# SCH_SPEAR.net
KiCad netlist of a schematic drawn in EasyEDA
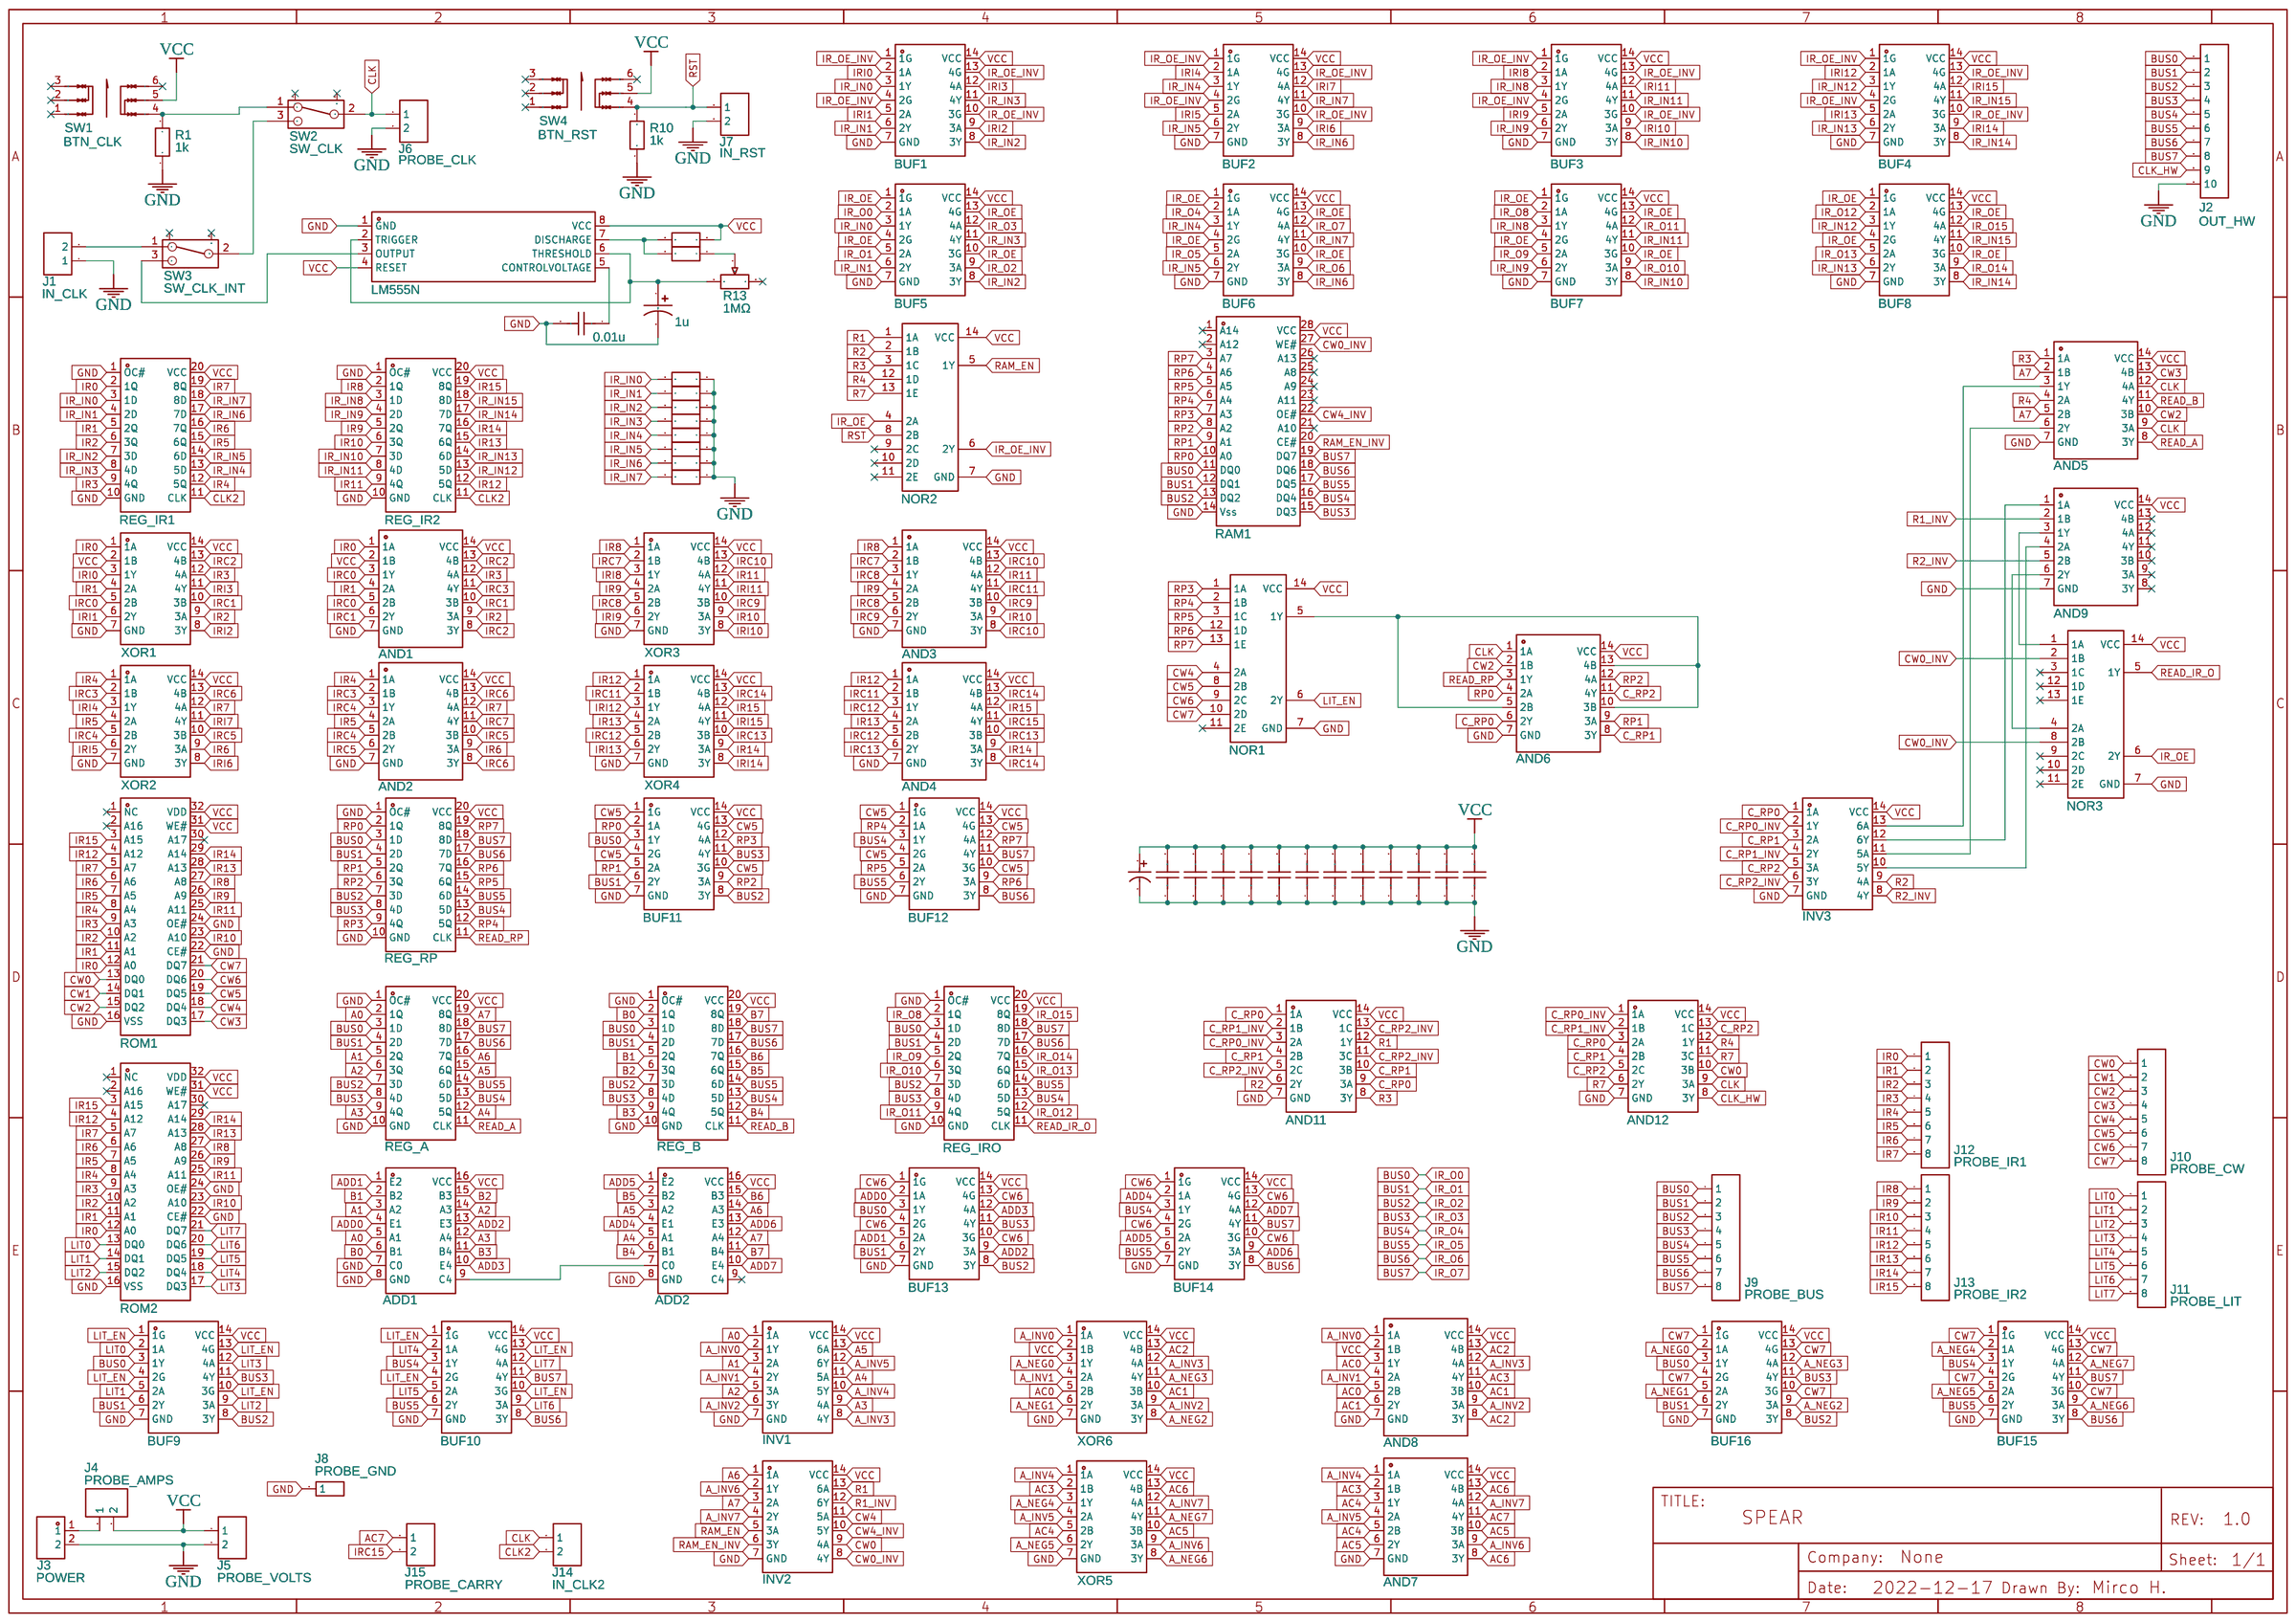
[diagram p0: schematic sheet]

(export (version "E")
  (design (tool "Eeschema 10.0.6"))
  (components
    (comp (ref "ADD1")
      (value "XD74LS283")
      (fields (field (name "BOM_Supplier Part") "C561301"))
      (libsource (lib "") (part "XD74LS283"))
    )
    (comp (ref "ADD2")
      (value "XD74LS283")
      (fields (field (name "BOM_Supplier Part") "C561301"))
      (libsource (lib "") (part "XD74LS283"))
    )
    (comp (ref "AND1")
      (value "SN74LS08DR")
      (fields (field (name "BOM_Supplier Part") "C6802"))
      (libsource (lib "") (part "SN74LS08DR"))
    )
    (comp (ref "AND2")
      (value "SN74LS08DR")
      (fields (field (name "BOM_Supplier Part") "C6802"))
      (libsource (lib "") (part "SN74LS08DR"))
    )
    (comp (ref "AND3")
      (value "SN74LS08DR")
      (fields (field (name "BOM_Supplier Part") "C6802"))
      (libsource (lib "") (part "SN74LS08DR"))
    )
    (comp (ref "AND4")
      (value "SN74LS08DR")
      (fields (field (name "BOM_Supplier Part") "C6802"))
      (libsource (lib "") (part "SN74LS08DR"))
    )
    (comp (ref "AND5")
      (value "SN74LS08DR")
      (fields (field (name "BOM_Supplier Part") "C6802"))
      (libsource (lib "") (part "SN74LS08DR"))
    )
    (comp (ref "AND6")
      (value "SN74LS08DR")
      (fields (field (name "BOM_Supplier Part") "C6802"))
      (libsource (lib "") (part "SN74LS08DR"))
    )
    (comp (ref "AND7")
      (value "SN74LS08DR")
      (fields (field (name "BOM_Supplier Part") "C6802"))
      (libsource (lib "") (part "SN74LS08DR"))
    )
    (comp (ref "AND8")
      (value "SN74LS08DR")
      (fields (field (name "BOM_Supplier Part") "C6802"))
      (libsource (lib "") (part "SN74LS08DR"))
    )
    (comp (ref "AND9")
      (value "SN74LS08DR")
      (fields (field (name "BOM_Supplier Part") "C6802"))
      (libsource (lib "") (part "SN74LS08DR"))
    )
    (comp (ref "AND11")
      (value "XL74LS11")
      (fields (field (name "BOM_Supplier Part") "C521168"))
      (libsource (lib "") (part "XL74LS11"))
    )
    (comp (ref "AND12")
      (value "XL74LS11")
      (fields (field (name "BOM_Supplier Part") "C521168"))
      (libsource (lib "") (part "XL74LS11"))
    )
    (comp (ref "BUF1")
      (value "SN74LS126ADR")
      (fields (field (name "BOM_Supplier Part") "C2865257"))
      (libsource (lib "") (part "SN74LS126ADR"))
    )
    (comp (ref "BUF2")
      (value "SN74LS126ADR")
      (fields (field (name "BOM_Supplier Part") "C2865257"))
      (libsource (lib "") (part "SN74LS126ADR"))
    )
    (comp (ref "BUF3")
      (value "SN74LS126ADR")
      (fields (field (name "BOM_Supplier Part") "C2865257"))
      (libsource (lib "") (part "SN74LS126ADR"))
    )
    (comp (ref "BUF4")
      (value "SN74LS126ADR")
      (fields (field (name "BOM_Supplier Part") "C2865257"))
      (libsource (lib "") (part "SN74LS126ADR"))
    )
    (comp (ref "BUF5")
      (value "SN74LS126ADR")
      (fields (field (name "BOM_Supplier Part") "C2865257"))
      (libsource (lib "") (part "SN74LS126ADR"))
    )
    (comp (ref "BUF6")
      (value "SN74LS126ADR")
      (fields (field (name "BOM_Supplier Part") "C2865257"))
      (libsource (lib "") (part "SN74LS126ADR"))
    )
    (comp (ref "BUF7")
      (value "SN74LS126ADR")
      (fields (field (name "BOM_Supplier Part") "C2865257"))
      (libsource (lib "") (part "SN74LS126ADR"))
    )
    (comp (ref "BUF8")
      (value "SN74LS126ADR")
      (fields (field (name "BOM_Supplier Part") "C2865257"))
      (libsource (lib "") (part "SN74LS126ADR"))
    )
    (comp (ref "BUF9")
      (value "SN74LS126ADR")
      (fields (field (name "BOM_Supplier Part") "C2865257"))
      (libsource (lib "") (part "SN74LS126ADR"))
    )
    (comp (ref "BUF10")
      (value "SN74LS126ADR")
      (fields (field (name "BOM_Supplier Part") "C2865257"))
      (libsource (lib "") (part "SN74LS126ADR"))
    )
    (comp (ref "BUF11")
      (value "SN74LS126ADR")
      (fields (field (name "BOM_Supplier Part") "C2865257"))
      (libsource (lib "") (part "SN74LS126ADR"))
    )
    (comp (ref "BUF12")
      (value "SN74LS126ADR")
      (fields (field (name "BOM_Supplier Part") "C2865257"))
      (libsource (lib "") (part "SN74LS126ADR"))
    )
    (comp (ref "BUF13")
      (value "SN74LS126ADR")
      (fields (field (name "BOM_Supplier Part") "C2865257"))
      (libsource (lib "") (part "SN74LS126ADR"))
    )
    (comp (ref "BUF14")
      (value "SN74LS126ADR")
      (fields (field (name "BOM_Supplier Part") "C2865257"))
      (libsource (lib "") (part "SN74LS126ADR"))
    )
    (comp (ref "BUF15")
      (value "SN74LS126ADR")
      (fields (field (name "BOM_Supplier Part") "C2865257"))
      (libsource (lib "") (part "SN74LS126ADR"))
    )
    (comp (ref "BUF16")
      (value "SN74LS126ADR")
      (fields (field (name "BOM_Supplier Part") "C2865257"))
      (libsource (lib "") (part "SN74LS126ADR"))
    )
    (comp (ref "C1") (value "0.1u") (libsource (lib "") (part "C_0603_US")))
    (comp (ref "C2") (value "0.01u") (libsource (lib "") (part "C_0603_US_1")))
    (comp (ref "C3") (value "1u") (libsource (lib "") (part "C_Tan_SMD_A_US")))
    (comp (ref "C4") (value "0.1u") (libsource (lib "") (part "C_0603_US")))
    (comp (ref "C5") (value "0.1u") (libsource (lib "") (part "C_0603_US")))
    (comp (ref "C6") (value "0.1u") (libsource (lib "") (part "C_0603_US")))
    (comp (ref "C7") (value "0.1u") (libsource (lib "") (part "C_0603_US")))
    (comp (ref "C8") (value "0.1u") (libsource (lib "") (part "C_0603_US")))
    (comp (ref "C9") (value "0.1u") (libsource (lib "") (part "C_0603_US")))
    (comp (ref "C10") (value "0.1u") (libsource (lib "") (part "C_0603_US")))
    (comp (ref "C11") (value "0.1u") (libsource (lib "") (part "C_0603_US")))
    (comp (ref "C12") (value "0.1u") (libsource (lib "") (part "C_0603_US")))
    (comp (ref "C13") (value "0.1u") (libsource (lib "") (part "C_0603_US")))
    (comp (ref "C14") (value "0.1u") (libsource (lib "") (part "C_0603_US")))
    (comp (ref "C15")
      (value "1000uF")
      (fields
        (field (name "BOM_Manufacturer Part") "KM108M025G17RR0VH2FP0")
        (field (name "BOM_Supplier Part") "C10750")
      )
      (libsource (lib "") (part "1000uF 25V"))
    )
    (comp (ref "INV1")
      (value "XL74LS04")
      (fields (field (name "BOM_Supplier Part") "C513511"))
      (libsource (lib "") (part "XL74LS04"))
    )
    (comp (ref "INV2")
      (value "XL74LS04")
      (fields (field (name "BOM_Supplier Part") "C513511"))
      (libsource (lib "") (part "XL74LS04"))
    )
    (comp (ref "INV3")
      (value "XL74LS04")
      (fields (field (name "BOM_Supplier Part") "C513511"))
      (libsource (lib "") (part "XL74LS04"))
    )
    (comp (ref "J1")
      (value "IN_CLK")
      (fields (field (name "BOM_Supplier Part") "C124375"))
      (libsource (lib "") (part "HDR-M-2.54_1x2"))
    )
    (comp (ref "J2")
      (value "OUT_HW")
      (fields (field (name "BOM_Supplier Part") "C57369"))
      (libsource (lib "") (part "HDR-M-2.54_1x10"))
    )
    (comp (ref "J3")
      (value "POWER")
      (fields
        (field (name "BOM_Manufacturer Part") "DB126V-5.0-2P-GN-P")
        (field (name "BOM_Supplier Part") "C395849")
      )
      (libsource (lib "") (part "DB126V-5.0-2P"))
    )
    (comp (ref "J4")
      (value "PROBE_AMPS")
      (fields (field (name "BOM_Supplier Part") "C124375"))
      (libsource (lib "") (part "HDR-M-2.54_1x2_2"))
    )
    (comp (ref "J5")
      (value "PROBE_VOLTS")
      (fields (field (name "BOM_Supplier Part") "C124375"))
      (libsource (lib "") (part "HDR-M-2.54_1x2_1"))
    )
    (comp (ref "J6")
      (value "PROBE_CLK")
      (fields (field (name "BOM_Supplier Part") "C124375"))
      (libsource (lib "") (part "HDR-M-2.54_1x2_1"))
    )
    (comp (ref "J7")
      (value "IN_RST")
      (fields (field (name "BOM_Supplier Part") "C124375"))
      (libsource (lib "") (part "HDR-M-2.54_1x2_1"))
    )
    (comp (ref "J8")
      (value "PROBE_GND")
      (fields (field (name "BOM_Supplier Part") "C81276"))
      (libsource (lib "") (part "HDR-M-2.54_1x1"))
    )
    (comp (ref "J9")
      (value "PROBE_BUS")
      (fields (field (name "BOM_Supplier Part") "C190820"))
      (libsource (lib "") (part "HDR-M-2.54_1x8"))
    )
    (comp (ref "J10")
      (value "PROBE_CW")
      (fields (field (name "BOM_Supplier Part") "C190820"))
      (libsource (lib "") (part "HDR-M-2.54_1x8"))
    )
    (comp (ref "J11")
      (value "PROBE_LIT")
      (fields (field (name "BOM_Supplier Part") "C190820"))
      (libsource (lib "") (part "HDR-M-2.54_1x8"))
    )
    (comp (ref "J12")
      (value "PROBE_IR1")
      (fields (field (name "BOM_Supplier Part") "C190820"))
      (libsource (lib "") (part "HDR-M-2.54_1x8"))
    )
    (comp (ref "J13")
      (value "PROBE_IR2")
      (fields (field (name "BOM_Supplier Part") "C190820"))
      (libsource (lib "") (part "HDR-M-2.54_1x8"))
    )
    (comp (ref "J14")
      (value "IN_CLK2")
      (fields (field (name "BOM_Supplier Part") "C124375"))
      (libsource (lib "") (part "HDR-M-2.54_1x2_1"))
    )
    (comp (ref "J15")
      (value "PROBE_CARRY")
      (fields (field (name "BOM_Supplier Part") "C124375"))
      (libsource (lib "") (part "HDR-M-2.54_1x2_1"))
    )
    (comp (ref "NOR1") (value "LISA_CPU_74LS260") (libsource (lib "") (part "LISA_CPU_74LS260")))
    (comp (ref "NOR2") (value "LISA_CPU_74LS260") (libsource (lib "") (part "LISA_CPU_74LS260")))
    (comp (ref "NOR3") (value "LISA_CPU_74LS260") (libsource (lib "") (part "LISA_CPU_74LS260")))
    (comp (ref "R1") (value "1k") (libsource (lib "") (part "R_0603_EU_1")))
    (comp (ref "R2") (value "10k") (libsource (lib "") (part "R_0603_EU")))
    (comp (ref "R3") (value "10k") (libsource (lib "") (part "R_0603_EU")))
    (comp (ref "R4") (value "10k") (libsource (lib "") (part "R_0603_EU")))
    (comp (ref "R5") (value "10k") (libsource (lib "") (part "R_0603_EU")))
    (comp (ref "R6") (value "10k") (libsource (lib "") (part "R_0603_EU")))
    (comp (ref "R7") (value "10k") (libsource (lib "") (part "R_0603_EU")))
    (comp (ref "R8") (value "10k") (libsource (lib "") (part "R_0603_EU")))
    (comp (ref "R9") (value "10k") (libsource (lib "") (part "R_0603_EU")))
    (comp (ref "R10") (value "1k") (libsource (lib "") (part "R_0603_EU_1")))
    (comp (ref "R11") (value "1k") (libsource (lib "") (part "R_0603_EU")))
    (comp (ref "R12") (value "1k") (libsource (lib "") (part "R_0603_EU")))
    (comp (ref "R13")
      (value "1MΩ")
      (fields
        (field (name "BOM_Manufacturer Part") "3362P-1-105")
        (field (name "BOM_Supplier Part") "C118945")
      )
      (libsource (lib "") (part "3362P-1-105_C118945"))
    )
    (comp (ref "RAM1")
      (value "LY62256SL-70LL")
      (fields (field (name "BOM_Supplier Part") "C261867"))
      (libsource (lib "") (part "LY62256SL-70LL"))
    )
    (comp (ref "REG1")
      (value "REG_IR1")
      (fields
        (field (name "BOM_Manufacturer Part") "SN74LS374NSR")
        (field (name "BOM_Supplier Part") "C7764")
      )
      (libsource (lib "") (part "SN74LS374NSR_2"))
    )
    (comp (ref "REG2")
      (value "REG_IR2")
      (fields
        (field (name "BOM_Manufacturer Part") "SN74LS374NSR")
        (field (name "BOM_Supplier Part") "C7764")
      )
      (libsource (lib "") (part "SN74LS374NSR_2"))
    )
    (comp (ref "REG_A")
      (value "SN74LS374NSR")
      (fields (field (name "BOM_Supplier Part") "C7764"))
      (libsource (lib "") (part "SN74LS374NSR_4"))
    )
    (comp (ref "REG_B")
      (value "SN74LS374NSR")
      (fields (field (name "BOM_Supplier Part") "C7764"))
      (libsource (lib "") (part "SN74LS374NSR"))
    )
    (comp (ref "REG_IRO")
      (value "SN74LS374NSR")
      (fields (field (name "BOM_Supplier Part") "C7764"))
      (libsource (lib "") (part "SN74LS374NSR_1"))
    )
    (comp (ref "REG_RP")
      (value "SN74LS374NSR")
      (fields (field (name "BOM_Supplier Part") "C7764"))
      (libsource (lib "") (part "SN74LS374NSR_3"))
    )
    (comp (ref "ROM1")
      (value "SST39SF020A-70-4I-NHE")
      (fields (field (name "BOM_Supplier Part") "C645934"))
      (libsource (lib "") (part "SST39SF020A-70-4I-NHE"))
    )
    (comp (ref "ROM2")
      (value "SST39SF020A-70-4I-NHE")
      (fields (field (name "BOM_Supplier Part") "C645934"))
      (libsource (lib "") (part "SST39SF020A-70-4I-NHE"))
    )
    (comp (ref "SW1")
      (value "BTN_CLK")
      (fields (field (name "BOM_Manufacturer Part") "XKB8080-W") (field (name "BOM_Supplier Part") "C318861"))
      (libsource (lib "") (part "XKB8080-W"))
    )
    (comp (ref "SW2")
      (value "SW_CLK")
      (fields
        (field (name "BOM_Manufacturer Part") "SK-12E12-G5")
        (field (name "BOM_Supplier Part") "C136720")
      )
      (libsource (lib "") (part "SK-12E12-G5"))
    )
    (comp (ref "SW3")
      (value "SW_CLK_INT")
      (fields
        (field (name "BOM_Manufacturer Part") "SK-12E12-G5")
        (field (name "BOM_Supplier Part") "C136720")
      )
      (libsource (lib "") (part "SK-12E12-G5"))
    )
    (comp (ref "SW4")
      (value "BTN_RST")
      (fields (field (name "BOM_Manufacturer Part") "XKB8080-W") (field (name "BOM_Supplier Part") "C318861"))
      (libsource (lib "") (part "XKB8080-W"))
    )
    (comp (ref "U1")
      (value "LM555N")
      (fields (field (name "BOM_Supplier Part") "C725327"))
      (libsource (lib "") (part "LM555N"))
    )
    (comp (ref "XOR1")
      (value "XD74LS86")
      (fields (field (name "BOM_Supplier Part") "C556290"))
      (libsource (lib "") (part "XD74LS86"))
    )
    (comp (ref "XOR2")
      (value "XD74LS86")
      (fields (field (name "BOM_Supplier Part") "C556290"))
      (libsource (lib "") (part "XD74LS86"))
    )
    (comp (ref "XOR3")
      (value "XD74LS86")
      (fields (field (name "BOM_Supplier Part") "C556290"))
      (libsource (lib "") (part "XD74LS86"))
    )
    (comp (ref "XOR4")
      (value "XD74LS86")
      (fields (field (name "BOM_Supplier Part") "C556290"))
      (libsource (lib "") (part "XD74LS86"))
    )
    (comp (ref "XOR5")
      (value "XD74LS86")
      (fields (field (name "BOM_Supplier Part") "C556290"))
      (libsource (lib "") (part "XD74LS86"))
    )
    (comp (ref "XOR6")
      (value "XD74LS86")
      (fields (field (name "BOM_Supplier Part") "C556290"))
      (libsource (lib "") (part "XD74LS86"))
    )
  )
  (nets
    (net (code "1") (name "A0") (class "Default")
      (node (ref "ADD1") (pin "5") (pinfunction "A1_5") (pintype "unspecified"))
      (node (ref "INV1") (pin "1") (pinfunction "1A_1") (pintype "unspecified"))
      (node (ref "REG_A") (pin "2") (pinfunction "1Q_2") (pintype "unspecified"))
    )
    (net (code "2") (name "A1") (class "Default")
      (node (ref "ADD1") (pin "3") (pinfunction "A2_3") (pintype "unspecified"))
      (node (ref "INV1") (pin "3") (pinfunction "2A_3") (pintype "unspecified"))
      (node (ref "REG_A") (pin "5") (pinfunction "2Q_5") (pintype "unspecified"))
    )
    (net (code "3") (name "A2") (class "Default")
      (node (ref "ADD1") (pin "14") (pinfunction "A3_14") (pintype "unspecified"))
      (node (ref "INV1") (pin "5") (pinfunction "3A_5") (pintype "unspecified"))
      (node (ref "REG_A") (pin "6") (pinfunction "3Q_6") (pintype "unspecified"))
    )
    (net (code "4") (name "A3") (class "Default")
      (node (ref "ADD1") (pin "12") (pinfunction "A4_12") (pintype "unspecified"))
      (node (ref "INV1") (pin "9") (pinfunction "4A_9") (pintype "unspecified"))
      (node (ref "REG_A") (pin "9") (pinfunction "4Q_9") (pintype "unspecified"))
    )
    (net (code "5") (name "A4") (class "Default")
      (node (ref "ADD2") (pin "5") (pinfunction "A1_5") (pintype "unspecified"))
      (node (ref "INV1") (pin "11") (pinfunction "5A_11") (pintype "unspecified"))
      (node (ref "REG_A") (pin "12") (pinfunction "5Q_12") (pintype "unspecified"))
    )
    (net (code "6") (name "A5") (class "Default")
      (node (ref "ADD2") (pin "3") (pinfunction "A2_3") (pintype "unspecified"))
      (node (ref "INV1") (pin "13") (pinfunction "6A_13") (pintype "unspecified"))
      (node (ref "REG_A") (pin "15") (pinfunction "6Q_15") (pintype "unspecified"))
    )
    (net (code "7") (name "A6") (class "Default")
      (node (ref "ADD2") (pin "14") (pinfunction "A3_14") (pintype "unspecified"))
      (node (ref "INV2") (pin "1") (pinfunction "1A_1") (pintype "unspecified"))
      (node (ref "REG_A") (pin "16") (pinfunction "7Q_16") (pintype "unspecified"))
    )
    (net (code "8") (name "A7") (class "Default")
      (node (ref "ADD2") (pin "12") (pinfunction "A4_12") (pintype "unspecified"))
      (node (ref "AND5") (pin "2") (pinfunction "1B_2") (pintype "unspecified"))
      (node (ref "AND5") (pin "5") (pinfunction "2B_5") (pintype "unspecified"))
      (node (ref "INV2") (pin "3") (pinfunction "2A_3") (pintype "unspecified"))
      (node (ref "REG_A") (pin "19") (pinfunction "8Q_19") (pintype "unspecified"))
    )
    (net (code "9") (name "AC0") (class "Default")
      (node (ref "AND8") (pin "3") (pinfunction "1Y_3") (pintype "unspecified"))
      (node (ref "AND8") (pin "5") (pinfunction "2B_5") (pintype "unspecified"))
      (node (ref "XOR6") (pin "5") (pinfunction "2B_5") (pintype "unspecified"))
    )
    (net (code "10") (name "AC1") (class "Default")
      (node (ref "AND8") (pin "10") (pinfunction "3B_10") (pintype "unspecified"))
      (node (ref "AND8") (pin "6") (pinfunction "2Y_6") (pintype "unspecified"))
      (node (ref "XOR6") (pin "10") (pinfunction "3B_10") (pintype "unspecified"))
    )
    (net (code "11") (name "AC2") (class "Default")
      (node (ref "AND8") (pin "13") (pinfunction "4B_13") (pintype "unspecified"))
      (node (ref "AND8") (pin "8") (pinfunction "3Y_8") (pintype "unspecified"))
      (node (ref "XOR6") (pin "13") (pinfunction "4B_13") (pintype "unspecified"))
    )
    (net (code "12") (name "AC3") (class "Default")
      (node (ref "AND7") (pin "2") (pinfunction "1B_2") (pintype "unspecified"))
      (node (ref "AND8") (pin "11") (pinfunction "4Y_11") (pintype "unspecified"))
      (node (ref "XOR5") (pin "2") (pinfunction "1B_2") (pintype "unspecified"))
    )
    (net (code "13") (name "AC4") (class "Default")
      (node (ref "AND7") (pin "3") (pinfunction "1Y_3") (pintype "unspecified"))
      (node (ref "AND7") (pin "5") (pinfunction "2B_5") (pintype "unspecified"))
      (node (ref "XOR5") (pin "5") (pinfunction "2B_5") (pintype "unspecified"))
    )
    (net (code "14") (name "AC5") (class "Default")
      (node (ref "AND7") (pin "10") (pinfunction "3B_10") (pintype "unspecified"))
      (node (ref "AND7") (pin "6") (pinfunction "2Y_6") (pintype "unspecified"))
      (node (ref "XOR5") (pin "10") (pinfunction "3B_10") (pintype "unspecified"))
    )
    (net (code "15") (name "AC6") (class "Default")
      (node (ref "AND7") (pin "13") (pinfunction "4B_13") (pintype "unspecified"))
      (node (ref "AND7") (pin "8") (pinfunction "3Y_8") (pintype "unspecified"))
      (node (ref "XOR5") (pin "13") (pinfunction "4B_13") (pintype "unspecified"))
    )
    (net (code "16") (name "AC7") (class "Default")
      (node (ref "AND7") (pin "11") (pinfunction "4Y_11") (pintype "unspecified"))
      (node (ref "J15") (pin "1") (pinfunction "1_1") (pintype "unspecified"))
    )
    (net (code "17") (name "ADD0") (class "Default")
      (node (ref "ADD1") (pin "4") (pinfunction "E1_4") (pintype "unspecified"))
      (node (ref "BUF13") (pin "2") (pinfunction "1A_2") (pintype "unspecified"))
    )
    (net (code "18") (name "ADD1") (class "Default")
      (node (ref "ADD1") (pin "1") (pinfunction "E2_1") (pintype "unspecified"))
      (node (ref "BUF13") (pin "5") (pinfunction "2A_5") (pintype "unspecified"))
    )
    (net (code "19") (name "ADD2") (class "Default")
      (node (ref "ADD1") (pin "13") (pinfunction "E3_13") (pintype "unspecified"))
      (node (ref "BUF13") (pin "9") (pinfunction "3A_9") (pintype "unspecified"))
    )
    (net (code "20") (name "ADD3") (class "Default")
      (node (ref "ADD1") (pin "10") (pinfunction "E4_10") (pintype "unspecified"))
      (node (ref "BUF13") (pin "12") (pinfunction "4A_12") (pintype "unspecified"))
    )
    (net (code "21") (name "ADD4") (class "Default")
      (node (ref "ADD2") (pin "4") (pinfunction "E1_4") (pintype "unspecified"))
      (node (ref "BUF14") (pin "2") (pinfunction "1A_2") (pintype "unspecified"))
    )
    (net (code "22") (name "ADD5") (class "Default")
      (node (ref "ADD2") (pin "1") (pinfunction "E2_1") (pintype "unspecified"))
      (node (ref "BUF14") (pin "5") (pinfunction "2A_5") (pintype "unspecified"))
    )
    (net (code "23") (name "ADD6") (class "Default")
      (node (ref "ADD2") (pin "13") (pinfunction "E3_13") (pintype "unspecified"))
      (node (ref "BUF14") (pin "9") (pinfunction "3A_9") (pintype "unspecified"))
    )
    (net (code "24") (name "ADD7") (class "Default")
      (node (ref "ADD2") (pin "10") (pinfunction "E4_10") (pintype "unspecified"))
      (node (ref "BUF14") (pin "12") (pinfunction "4A_12") (pintype "unspecified"))
    )
    (net (code "25") (name "A_INV0") (class "Default")
      (node (ref "AND8") (pin "1") (pinfunction "1A_1") (pintype "unspecified"))
      (node (ref "INV1") (pin "2") (pinfunction "1Y_2") (pintype "unspecified"))
      (node (ref "XOR6") (pin "1") (pinfunction "1A_1") (pintype "unspecified"))
    )
    (net (code "26") (name "A_INV1") (class "Default")
      (node (ref "AND8") (pin "4") (pinfunction "2A_4") (pintype "unspecified"))
      (node (ref "INV1") (pin "4") (pinfunction "2Y_4") (pintype "unspecified"))
      (node (ref "XOR6") (pin "4") (pinfunction "2A_4") (pintype "unspecified"))
    )
    (net (code "27") (name "A_INV2") (class "Default")
      (node (ref "AND8") (pin "9") (pinfunction "3A_9") (pintype "unspecified"))
      (node (ref "INV1") (pin "6") (pinfunction "3Y_6") (pintype "unspecified"))
      (node (ref "XOR6") (pin "9") (pinfunction "3A_9") (pintype "unspecified"))
    )
    (net (code "28") (name "A_INV3") (class "Default")
      (node (ref "AND8") (pin "12") (pinfunction "4A_12") (pintype "unspecified"))
      (node (ref "INV1") (pin "8") (pinfunction "4Y_8") (pintype "unspecified"))
      (node (ref "XOR6") (pin "12") (pinfunction "4A_12") (pintype "unspecified"))
    )
    (net (code "29") (name "A_INV4") (class "Default")
      (node (ref "AND7") (pin "1") (pinfunction "1A_1") (pintype "unspecified"))
      (node (ref "INV1") (pin "10") (pinfunction "5Y_10") (pintype "unspecified"))
      (node (ref "XOR5") (pin "1") (pinfunction "1A_1") (pintype "unspecified"))
    )
    (net (code "30") (name "A_INV5") (class "Default")
      (node (ref "AND7") (pin "4") (pinfunction "2A_4") (pintype "unspecified"))
      (node (ref "INV1") (pin "12") (pinfunction "6Y_12") (pintype "unspecified"))
      (node (ref "XOR5") (pin "4") (pinfunction "2A_4") (pintype "unspecified"))
    )
    (net (code "31") (name "A_INV6") (class "Default")
      (node (ref "AND7") (pin "9") (pinfunction "3A_9") (pintype "unspecified"))
      (node (ref "INV2") (pin "2") (pinfunction "1Y_2") (pintype "unspecified"))
      (node (ref "XOR5") (pin "9") (pinfunction "3A_9") (pintype "unspecified"))
    )
    (net (code "32") (name "A_INV7") (class "Default")
      (node (ref "AND7") (pin "12") (pinfunction "4A_12") (pintype "unspecified"))
      (node (ref "INV2") (pin "4") (pinfunction "2Y_4") (pintype "unspecified"))
      (node (ref "XOR5") (pin "12") (pinfunction "4A_12") (pintype "unspecified"))
    )
    (net (code "33") (name "A_NEG0") (class "Default")
      (node (ref "BUF16") (pin "2") (pinfunction "1A_2") (pintype "unspecified"))
      (node (ref "XOR6") (pin "3") (pinfunction "1Y_3") (pintype "unspecified"))
    )
    (net (code "34") (name "A_NEG1") (class "Default")
      (node (ref "BUF16") (pin "5") (pinfunction "2A_5") (pintype "unspecified"))
      (node (ref "XOR6") (pin "6") (pinfunction "2Y_6") (pintype "unspecified"))
    )
    (net (code "35") (name "A_NEG2") (class "Default")
      (node (ref "BUF16") (pin "9") (pinfunction "3A_9") (pintype "unspecified"))
      (node (ref "XOR6") (pin "8") (pinfunction "3Y_8") (pintype "unspecified"))
    )
    (net (code "36") (name "A_NEG3") (class "Default")
      (node (ref "BUF16") (pin "12") (pinfunction "4A_12") (pintype "unspecified"))
      (node (ref "XOR6") (pin "11") (pinfunction "4Y_11") (pintype "unspecified"))
    )
    (net (code "37") (name "A_NEG4") (class "Default")
      (node (ref "BUF15") (pin "2") (pinfunction "1A_2") (pintype "unspecified"))
      (node (ref "XOR5") (pin "3") (pinfunction "1Y_3") (pintype "unspecified"))
    )
    (net (code "38") (name "A_NEG5") (class "Default")
      (node (ref "BUF15") (pin "5") (pinfunction "2A_5") (pintype "unspecified"))
      (node (ref "XOR5") (pin "6") (pinfunction "2Y_6") (pintype "unspecified"))
    )
    (net (code "39") (name "A_NEG6") (class "Default")
      (node (ref "BUF15") (pin "9") (pinfunction "3A_9") (pintype "unspecified"))
      (node (ref "XOR5") (pin "8") (pinfunction "3Y_8") (pintype "unspecified"))
    )
    (net (code "40") (name "A_NEG7") (class "Default")
      (node (ref "BUF15") (pin "12") (pinfunction "4A_12") (pintype "unspecified"))
      (node (ref "XOR5") (pin "11") (pinfunction "4Y_11") (pintype "unspecified"))
    )
    (net (code "41") (name "B0") (class "Default")
      (node (ref "ADD1") (pin "6") (pinfunction "B1_6") (pintype "unspecified"))
      (node (ref "REG_B") (pin "2") (pinfunction "1Q_2") (pintype "unspecified"))
    )
    (net (code "42") (name "B1") (class "Default")
      (node (ref "ADD1") (pin "2") (pinfunction "B2_2") (pintype "unspecified"))
      (node (ref "REG_B") (pin "5") (pinfunction "2Q_5") (pintype "unspecified"))
    )
    (net (code "43") (name "B2") (class "Default")
      (node (ref "ADD1") (pin "15") (pinfunction "B3_15") (pintype "unspecified"))
      (node (ref "REG_B") (pin "6") (pinfunction "3Q_6") (pintype "unspecified"))
    )
    (net (code "44") (name "B3") (class "Default")
      (node (ref "ADD1") (pin "11") (pinfunction "B4_11") (pintype "unspecified"))
      (node (ref "REG_B") (pin "9") (pinfunction "4Q_9") (pintype "unspecified"))
    )
    (net (code "45") (name "B4") (class "Default")
      (node (ref "ADD2") (pin "6") (pinfunction "B1_6") (pintype "unspecified"))
      (node (ref "REG_B") (pin "12") (pinfunction "5Q_12") (pintype "unspecified"))
    )
    (net (code "46") (name "B5") (class "Default")
      (node (ref "ADD2") (pin "2") (pinfunction "B2_2") (pintype "unspecified"))
      (node (ref "REG_B") (pin "15") (pinfunction "6Q_15") (pintype "unspecified"))
    )
    (net (code "47") (name "B6") (class "Default")
      (node (ref "ADD2") (pin "15") (pinfunction "B3_15") (pintype "unspecified"))
      (node (ref "REG_B") (pin "16") (pinfunction "7Q_16") (pintype "unspecified"))
    )
    (net (code "48") (name "B7") (class "Default")
      (node (ref "ADD2") (pin "11") (pinfunction "B4_11") (pintype "unspecified"))
      (node (ref "REG_B") (pin "19") (pinfunction "8Q_19") (pintype "unspecified"))
    )
    (net (code "49") (name "BUS0") (class "Default")
      (node (ref "BUF11") (pin "3") (pinfunction "1Y_3") (pintype "unspecified"))
      (node (ref "BUF13") (pin "3") (pinfunction "1Y_3") (pintype "unspecified"))
      (node (ref "BUF16") (pin "3") (pinfunction "1Y_3") (pintype "unspecified"))
      (node (ref "BUF5") (pin "2") (pinfunction "1A_2") (pintype "unspecified"))
      (node (ref "BUF9") (pin "3") (pinfunction "1Y_3") (pintype "unspecified"))
      (node (ref "J2") (pin "1") (pinfunction "1_1") (pintype "unspecified"))
      (node (ref "J9") (pin "1") (pinfunction "1_1") (pintype "unspecified"))
      (node (ref "RAM1") (pin "11") (pinfunction "DQ0_11") (pintype "unspecified"))
      (node (ref "REG_A") (pin "3") (pinfunction "1D_3") (pintype "unspecified"))
      (node (ref "REG_B") (pin "3") (pinfunction "1D_3") (pintype "unspecified"))
      (node (ref "REG_IRO") (pin "3") (pinfunction "1D_3") (pintype "unspecified"))
      (node (ref "REG_RP") (pin "3") (pinfunction "1D_3") (pintype "unspecified"))
    )
    (net (code "50") (name "BUS1") (class "Default")
      (node (ref "BUF11") (pin "6") (pinfunction "2Y_6") (pintype "unspecified"))
      (node (ref "BUF13") (pin "6") (pinfunction "2Y_6") (pintype "unspecified"))
      (node (ref "BUF16") (pin "6") (pinfunction "2Y_6") (pintype "unspecified"))
      (node (ref "BUF5") (pin "5") (pinfunction "2A_5") (pintype "unspecified"))
      (node (ref "BUF9") (pin "6") (pinfunction "2Y_6") (pintype "unspecified"))
      (node (ref "J2") (pin "2") (pinfunction "2_2") (pintype "unspecified"))
      (node (ref "J9") (pin "2") (pinfunction "2_2") (pintype "unspecified"))
      (node (ref "RAM1") (pin "12") (pinfunction "DQ1_12") (pintype "unspecified"))
      (node (ref "REG_A") (pin "4") (pinfunction "2D_4") (pintype "unspecified"))
      (node (ref "REG_B") (pin "4") (pinfunction "2D_4") (pintype "unspecified"))
      (node (ref "REG_IRO") (pin "4") (pinfunction "2D_4") (pintype "unspecified"))
      (node (ref "REG_RP") (pin "4") (pinfunction "2D_4") (pintype "unspecified"))
    )
    (net (code "51") (name "BUS2") (class "Default")
      (node (ref "BUF11") (pin "8") (pinfunction "3Y_8") (pintype "unspecified"))
      (node (ref "BUF13") (pin "8") (pinfunction "3Y_8") (pintype "unspecified"))
      (node (ref "BUF16") (pin "8") (pinfunction "3Y_8") (pintype "unspecified"))
      (node (ref "BUF5") (pin "9") (pinfunction "3A_9") (pintype "unspecified"))
      (node (ref "BUF9") (pin "8") (pinfunction "3Y_8") (pintype "unspecified"))
      (node (ref "J2") (pin "3") (pinfunction "3_3") (pintype "unspecified"))
      (node (ref "J9") (pin "3") (pinfunction "3_3") (pintype "unspecified"))
      (node (ref "RAM1") (pin "13") (pinfunction "DQ2_13") (pintype "unspecified"))
      (node (ref "REG_A") (pin "7") (pinfunction "3D_7") (pintype "unspecified"))
      (node (ref "REG_B") (pin "7") (pinfunction "3D_7") (pintype "unspecified"))
      (node (ref "REG_IRO") (pin "7") (pinfunction "3D_7") (pintype "unspecified"))
      (node (ref "REG_RP") (pin "7") (pinfunction "3D_7") (pintype "unspecified"))
    )
    (net (code "52") (name "BUS3") (class "Default")
      (node (ref "BUF11") (pin "11") (pinfunction "4Y_11") (pintype "unspecified"))
      (node (ref "BUF13") (pin "11") (pinfunction "4Y_11") (pintype "unspecified"))
      (node (ref "BUF16") (pin "11") (pinfunction "4Y_11") (pintype "unspecified"))
      (node (ref "BUF5") (pin "12") (pinfunction "4A_12") (pintype "unspecified"))
      (node (ref "BUF9") (pin "11") (pinfunction "4Y_11") (pintype "unspecified"))
      (node (ref "J2") (pin "4") (pinfunction "4_4") (pintype "unspecified"))
      (node (ref "J9") (pin "4") (pinfunction "4_4") (pintype "unspecified"))
      (node (ref "RAM1") (pin "15") (pinfunction "DQ3_15") (pintype "unspecified"))
      (node (ref "REG_A") (pin "8") (pinfunction "4D_8") (pintype "unspecified"))
      (node (ref "REG_B") (pin "8") (pinfunction "4D_8") (pintype "unspecified"))
      (node (ref "REG_IRO") (pin "8") (pinfunction "4D_8") (pintype "unspecified"))
      (node (ref "REG_RP") (pin "8") (pinfunction "4D_8") (pintype "unspecified"))
    )
    (net (code "53") (name "BUS4") (class "Default")
      (node (ref "BUF10") (pin "3") (pinfunction "1Y_3") (pintype "unspecified"))
      (node (ref "BUF12") (pin "3") (pinfunction "1Y_3") (pintype "unspecified"))
      (node (ref "BUF14") (pin "3") (pinfunction "1Y_3") (pintype "unspecified"))
      (node (ref "BUF15") (pin "3") (pinfunction "1Y_3") (pintype "unspecified"))
      (node (ref "BUF6") (pin "2") (pinfunction "1A_2") (pintype "unspecified"))
      (node (ref "J2") (pin "5") (pinfunction "5_5") (pintype "unspecified"))
      (node (ref "J9") (pin "5") (pinfunction "5_5") (pintype "unspecified"))
      (node (ref "RAM1") (pin "16") (pinfunction "DQ4_16") (pintype "unspecified"))
      (node (ref "REG_A") (pin "13") (pinfunction "5D_13") (pintype "unspecified"))
      (node (ref "REG_B") (pin "13") (pinfunction "5D_13") (pintype "unspecified"))
      (node (ref "REG_IRO") (pin "13") (pinfunction "5D_13") (pintype "unspecified"))
      (node (ref "REG_RP") (pin "13") (pinfunction "5D_13") (pintype "unspecified"))
    )
    (net (code "54") (name "BUS5") (class "Default")
      (node (ref "BUF10") (pin "6") (pinfunction "2Y_6") (pintype "unspecified"))
      (node (ref "BUF12") (pin "6") (pinfunction "2Y_6") (pintype "unspecified"))
      (node (ref "BUF14") (pin "6") (pinfunction "2Y_6") (pintype "unspecified"))
      (node (ref "BUF15") (pin "6") (pinfunction "2Y_6") (pintype "unspecified"))
      (node (ref "BUF6") (pin "5") (pinfunction "2A_5") (pintype "unspecified"))
      (node (ref "J2") (pin "6") (pinfunction "6_6") (pintype "unspecified"))
      (node (ref "J9") (pin "6") (pinfunction "6_6") (pintype "unspecified"))
      (node (ref "RAM1") (pin "17") (pinfunction "DQ5_17") (pintype "unspecified"))
      (node (ref "REG_A") (pin "14") (pinfunction "6D_14") (pintype "unspecified"))
      (node (ref "REG_B") (pin "14") (pinfunction "6D_14") (pintype "unspecified"))
      (node (ref "REG_IRO") (pin "14") (pinfunction "6D_14") (pintype "unspecified"))
      (node (ref "REG_RP") (pin "14") (pinfunction "6D_14") (pintype "unspecified"))
    )
    (net (code "55") (name "BUS6") (class "Default")
      (node (ref "BUF10") (pin "8") (pinfunction "3Y_8") (pintype "unspecified"))
      (node (ref "BUF12") (pin "8") (pinfunction "3Y_8") (pintype "unspecified"))
      (node (ref "BUF14") (pin "8") (pinfunction "3Y_8") (pintype "unspecified"))
      (node (ref "BUF15") (pin "8") (pinfunction "3Y_8") (pintype "unspecified"))
      (node (ref "BUF6") (pin "9") (pinfunction "3A_9") (pintype "unspecified"))
      (node (ref "J2") (pin "7") (pinfunction "7_7") (pintype "unspecified"))
      (node (ref "J9") (pin "7") (pinfunction "7_7") (pintype "unspecified"))
      (node (ref "RAM1") (pin "18") (pinfunction "DQ6_18") (pintype "unspecified"))
      (node (ref "REG_A") (pin "17") (pinfunction "7D_17") (pintype "unspecified"))
      (node (ref "REG_B") (pin "17") (pinfunction "7D_17") (pintype "unspecified"))
      (node (ref "REG_IRO") (pin "17") (pinfunction "7D_17") (pintype "unspecified"))
      (node (ref "REG_RP") (pin "17") (pinfunction "7D_17") (pintype "unspecified"))
    )
    (net (code "56") (name "BUS7") (class "Default")
      (node (ref "BUF10") (pin "11") (pinfunction "4Y_11") (pintype "unspecified"))
      (node (ref "BUF12") (pin "11") (pinfunction "4Y_11") (pintype "unspecified"))
      (node (ref "BUF14") (pin "11") (pinfunction "4Y_11") (pintype "unspecified"))
      (node (ref "BUF15") (pin "11") (pinfunction "4Y_11") (pintype "unspecified"))
      (node (ref "BUF6") (pin "12") (pinfunction "4A_12") (pintype "unspecified"))
      (node (ref "J2") (pin "8") (pinfunction "8_8") (pintype "unspecified"))
      (node (ref "J9") (pin "8") (pinfunction "8_8") (pintype "unspecified"))
      (node (ref "RAM1") (pin "19") (pinfunction "DQ7_19") (pintype "unspecified"))
      (node (ref "REG_A") (pin "18") (pinfunction "8D_18") (pintype "unspecified"))
      (node (ref "REG_B") (pin "18") (pinfunction "8D_18") (pintype "unspecified"))
      (node (ref "REG_IRO") (pin "18") (pinfunction "8D_18") (pintype "unspecified"))
      (node (ref "REG_RP") (pin "18") (pinfunction "8D_18") (pintype "unspecified"))
    )
    (net (code "57") (name "CLK") (class "Default")
      (node (ref "AND12") (pin "9") (pinfunction "3A_9") (pintype "unspecified"))
      (node (ref "AND5") (pin "12") (pinfunction "4A_12") (pintype "unspecified"))
      (node (ref "AND5") (pin "9") (pinfunction "3A_9") (pintype "unspecified"))
      (node (ref "AND6") (pin "1") (pinfunction "1A_1") (pintype "unspecified"))
      (node (ref "J14") (pin "1") (pinfunction "1_1") (pintype "unspecified"))
      (node (ref "J6") (pin "1") (pinfunction "1_1") (pintype "unspecified"))
      (node (ref "SW2") (pin "2") (pinfunction "2_2") (pintype "unspecified"))
    )
    (net (code "58") (name "CLK2") (class "Default")
      (node (ref "J14") (pin "2") (pinfunction "2_2") (pintype "unspecified"))
      (node (ref "REG1") (pin "11") (pinfunction "CLK_11") (pintype "unspecified"))
      (node (ref "REG2") (pin "11") (pinfunction "CLK_11") (pintype "unspecified"))
    )
    (net (code "59") (name "CLK_HW") (class "Default")
      (node (ref "AND12") (pin "8") (pinfunction "3Y_8") (pintype "unspecified"))
      (node (ref "J2") (pin "9") (pinfunction "9_9") (pintype "unspecified"))
    )
    (net (code "60") (name "CW0") (class "Default")
      (node (ref "AND12") (pin "10") (pinfunction "3B_10") (pintype "unspecified"))
      (node (ref "INV2") (pin "9") (pinfunction "4A_9") (pintype "unspecified"))
      (node (ref "J10") (pin "1") (pinfunction "1_1") (pintype "unspecified"))
      (node (ref "ROM1") (pin "13") (pinfunction "DQ0_13") (pintype "unspecified"))
    )
    (net (code "61") (name "CW0_INV") (class "Default")
      (node (ref "INV2") (pin "8") (pinfunction "4Y_8") (pintype "unspecified"))
      (node (ref "NOR3") (pin "2") (pinfunction "1B_2") (pintype "unspecified"))
      (node (ref "NOR3") (pin "8") (pinfunction "2B_8") (pintype "unspecified"))
      (node (ref "RAM1") (pin "27") (pinfunction "WE#_27") (pintype "unspecified"))
    )
    (net (code "62") (name "CW1") (class "Default")
      (node (ref "J10") (pin "2") (pinfunction "2_2") (pintype "unspecified"))
      (node (ref "ROM1") (pin "14") (pinfunction "DQ1_14") (pintype "unspecified"))
    )
    (net (code "63") (name "CW2") (class "Default")
      (node (ref "AND5") (pin "10") (pinfunction "3B_10") (pintype "unspecified"))
      (node (ref "AND6") (pin "2") (pinfunction "1B_2") (pintype "unspecified"))
      (node (ref "J10") (pin "3") (pinfunction "3_3") (pintype "unspecified"))
      (node (ref "ROM1") (pin "15") (pinfunction "DQ2_15") (pintype "unspecified"))
    )
    (net (code "64") (name "CW3") (class "Default")
      (node (ref "AND5") (pin "13") (pinfunction "4B_13") (pintype "unspecified"))
      (node (ref "J10") (pin "4") (pinfunction "4_4") (pintype "unspecified"))
      (node (ref "ROM1") (pin "17") (pinfunction "DQ3_17") (pintype "unspecified"))
    )
    (net (code "65") (name "CW4") (class "Default")
      (node (ref "INV2") (pin "11") (pinfunction "5A_11") (pintype "unspecified"))
      (node (ref "J10") (pin "5") (pinfunction "5_5") (pintype "unspecified"))
      (node (ref "NOR1") (pin "4") (pinfunction "2A_4") (pintype "unspecified"))
      (node (ref "ROM1") (pin "18") (pinfunction "DQ4_18") (pintype "unspecified"))
    )
    (net (code "66") (name "CW4_INV") (class "Default")
      (node (ref "INV2") (pin "10") (pinfunction "5Y_10") (pintype "unspecified"))
      (node (ref "RAM1") (pin "22") (pinfunction "OE#_22") (pintype "unspecified"))
    )
    (net (code "67") (name "CW5") (class "Default")
      (node (ref "BUF11") (pin "1") (pinfunction "1G_1") (pintype "unspecified"))
      (node (ref "BUF11") (pin "10") (pinfunction "3G_10") (pintype "unspecified"))
      (node (ref "BUF11") (pin "13") (pinfunction "4G_13") (pintype "unspecified"))
      (node (ref "BUF11") (pin "4") (pinfunction "2G_4") (pintype "unspecified"))
      (node (ref "BUF12") (pin "1") (pinfunction "1G_1") (pintype "unspecified"))
      (node (ref "BUF12") (pin "10") (pinfunction "3G_10") (pintype "unspecified"))
      (node (ref "BUF12") (pin "13") (pinfunction "4G_13") (pintype "unspecified"))
      (node (ref "BUF12") (pin "4") (pinfunction "2G_4") (pintype "unspecified"))
      (node (ref "J10") (pin "6") (pinfunction "6_6") (pintype "unspecified"))
      (node (ref "NOR1") (pin "8") (pinfunction "2B_8") (pintype "unspecified"))
      (node (ref "ROM1") (pin "19") (pinfunction "DQ5_19") (pintype "unspecified"))
    )
    (net (code "68") (name "CW6") (class "Default")
      (node (ref "BUF13") (pin "1") (pinfunction "1G_1") (pintype "unspecified"))
      (node (ref "BUF13") (pin "10") (pinfunction "3G_10") (pintype "unspecified"))
      (node (ref "BUF13") (pin "13") (pinfunction "4G_13") (pintype "unspecified"))
      (node (ref "BUF13") (pin "4") (pinfunction "2G_4") (pintype "unspecified"))
      (node (ref "BUF14") (pin "1") (pinfunction "1G_1") (pintype "unspecified"))
      (node (ref "BUF14") (pin "10") (pinfunction "3G_10") (pintype "unspecified"))
      (node (ref "BUF14") (pin "13") (pinfunction "4G_13") (pintype "unspecified"))
      (node (ref "BUF14") (pin "4") (pinfunction "2G_4") (pintype "unspecified"))
      (node (ref "J10") (pin "7") (pinfunction "7_7") (pintype "unspecified"))
      (node (ref "NOR1") (pin "9") (pinfunction "2C_9") (pintype "unspecified"))
      (node (ref "ROM1") (pin "20") (pinfunction "DQ6_20") (pintype "unspecified"))
    )
    (net (code "69") (name "CW7") (class "Default")
      (node (ref "BUF15") (pin "1") (pinfunction "1G_1") (pintype "unspecified"))
      (node (ref "BUF15") (pin "10") (pinfunction "3G_10") (pintype "unspecified"))
      (node (ref "BUF15") (pin "13") (pinfunction "4G_13") (pintype "unspecified"))
      (node (ref "BUF15") (pin "4") (pinfunction "2G_4") (pintype "unspecified"))
      (node (ref "BUF16") (pin "1") (pinfunction "1G_1") (pintype "unspecified"))
      (node (ref "BUF16") (pin "10") (pinfunction "3G_10") (pintype "unspecified"))
      (node (ref "BUF16") (pin "13") (pinfunction "4G_13") (pintype "unspecified"))
      (node (ref "BUF16") (pin "4") (pinfunction "2G_4") (pintype "unspecified"))
      (node (ref "J10") (pin "8") (pinfunction "8_8") (pintype "unspecified"))
      (node (ref "NOR1") (pin "10") (pinfunction "2D_10") (pintype "unspecified"))
      (node (ref "ROM1") (pin "21") (pinfunction "DQ7_21") (pintype "unspecified"))
    )
    (net (code "70") (name "C_RP0") (class "Default")
      (node (ref "AND11") (pin "1") (pinfunction "1A_1") (pintype "unspecified"))
      (node (ref "AND11") (pin "9") (pinfunction "3A_9") (pintype "unspecified"))
      (node (ref "AND12") (pin "3") (pinfunction "2A_3") (pintype "unspecified"))
      (node (ref "AND6") (pin "6") (pinfunction "2Y_6") (pintype "unspecified"))
      (node (ref "INV3") (pin "1") (pinfunction "1A_1") (pintype "unspecified"))
    )
    (net (code "71") (name "C_RP0_INV") (class "Default")
      (node (ref "AND11") (pin "3") (pinfunction "2A_3") (pintype "unspecified"))
      (node (ref "AND12") (pin "1") (pinfunction "1A_1") (pintype "unspecified"))
      (node (ref "INV3") (pin "2") (pinfunction "1Y_2") (pintype "unspecified"))
    )
    (net (code "72") (name "C_RP1") (class "Default")
      (node (ref "AND11") (pin "10") (pinfunction "3B_10") (pintype "unspecified"))
      (node (ref "AND11") (pin "4") (pinfunction "2B_4") (pintype "unspecified"))
      (node (ref "AND12") (pin "4") (pinfunction "2B_4") (pintype "unspecified"))
      (node (ref "AND6") (pin "8") (pinfunction "3Y_8") (pintype "unspecified"))
      (node (ref "INV3") (pin "3") (pinfunction "2A_3") (pintype "unspecified"))
    )
    (net (code "73") (name "C_RP1_INV") (class "Default")
      (node (ref "AND11") (pin "2") (pinfunction "1B_2") (pintype "unspecified"))
      (node (ref "AND12") (pin "2") (pinfunction "1B_2") (pintype "unspecified"))
      (node (ref "INV3") (pin "4") (pinfunction "2Y_4") (pintype "unspecified"))
    )
    (net (code "74") (name "C_RP2") (class "Default")
      (node (ref "AND12") (pin "13") (pinfunction "1C_13") (pintype "unspecified"))
      (node (ref "AND12") (pin "5") (pinfunction "2C_5") (pintype "unspecified"))
      (node (ref "AND6") (pin "11") (pinfunction "4Y_11") (pintype "unspecified"))
      (node (ref "INV3") (pin "5") (pinfunction "3A_5") (pintype "unspecified"))
    )
    (net (code "75") (name "C_RP2_INV") (class "Default")
      (node (ref "AND11") (pin "11") (pinfunction "3C_11") (pintype "unspecified"))
      (node (ref "AND11") (pin "13") (pinfunction "1C_13") (pintype "unspecified"))
      (node (ref "AND11") (pin "5") (pinfunction "2C_5") (pintype "unspecified"))
      (node (ref "INV3") (pin "6") (pinfunction "3Y_6") (pintype "unspecified"))
    )
    (net (code "76") (name "GND") (class "Default")
      (node (ref "ADD1") (pin "7") (pinfunction "C0_7") (pintype "unspecified"))
      (node (ref "ADD1") (pin "8") (pinfunction "GND_8") (pintype "unspecified"))
      (node (ref "ADD2") (pin "8") (pinfunction "GND_8") (pintype "unspecified"))
      (node (ref "AND1") (pin "7") (pinfunction "GND_7") (pintype "unspecified"))
      (node (ref "AND11") (pin "7") (pinfunction "GND_7") (pintype "unspecified"))
      (node (ref "AND12") (pin "7") (pinfunction "GND_7") (pintype "unspecified"))
      (node (ref "AND2") (pin "7") (pinfunction "GND_7") (pintype "unspecified"))
      (node (ref "AND3") (pin "7") (pinfunction "GND_7") (pintype "unspecified"))
      (node (ref "AND4") (pin "7") (pinfunction "GND_7") (pintype "unspecified"))
      (node (ref "AND5") (pin "7") (pinfunction "GND_7") (pintype "unspecified"))
      (node (ref "AND6") (pin "7") (pinfunction "GND_7") (pintype "unspecified"))
      (node (ref "AND7") (pin "7") (pinfunction "GND_7") (pintype "unspecified"))
      (node (ref "AND8") (pin "7") (pinfunction "GND_7") (pintype "unspecified"))
      (node (ref "AND9") (pin "7") (pinfunction "GND_7") (pintype "unspecified"))
      (node (ref "BUF1") (pin "7") (pinfunction "GND_7") (pintype "unspecified"))
      (node (ref "BUF10") (pin "7") (pinfunction "GND_7") (pintype "unspecified"))
      (node (ref "BUF11") (pin "7") (pinfunction "GND_7") (pintype "unspecified"))
      (node (ref "BUF12") (pin "7") (pinfunction "GND_7") (pintype "unspecified"))
      (node (ref "BUF13") (pin "7") (pinfunction "GND_7") (pintype "unspecified"))
      (node (ref "BUF14") (pin "7") (pinfunction "GND_7") (pintype "unspecified"))
      (node (ref "BUF15") (pin "7") (pinfunction "GND_7") (pintype "unspecified"))
      (node (ref "BUF16") (pin "7") (pinfunction "GND_7") (pintype "unspecified"))
      (node (ref "BUF2") (pin "7") (pinfunction "GND_7") (pintype "unspecified"))
      (node (ref "BUF3") (pin "7") (pinfunction "GND_7") (pintype "unspecified"))
      (node (ref "BUF4") (pin "7") (pinfunction "GND_7") (pintype "unspecified"))
      (node (ref "BUF5") (pin "7") (pinfunction "GND_7") (pintype "unspecified"))
      (node (ref "BUF6") (pin "7") (pinfunction "GND_7") (pintype "unspecified"))
      (node (ref "BUF7") (pin "7") (pinfunction "GND_7") (pintype "unspecified"))
      (node (ref "BUF8") (pin "7") (pinfunction "GND_7") (pintype "unspecified"))
      (node (ref "BUF9") (pin "7") (pinfunction "GND_7") (pintype "unspecified"))
      (node (ref "C1") (pin "1") (pinfunction "1_1") (pintype "unspecified"))
      (node (ref "C10") (pin "1") (pinfunction "1_1") (pintype "unspecified"))
      (node (ref "C11") (pin "1") (pinfunction "1_1") (pintype "unspecified"))
      (node (ref "C12") (pin "1") (pinfunction "1_1") (pintype "unspecified"))
      (node (ref "C13") (pin "1") (pinfunction "1_1") (pintype "unspecified"))
      (node (ref "C14") (pin "1") (pinfunction "1_1") (pintype "unspecified"))
      (node (ref "C15") (pin "2") (pinfunction "2_2") (pintype "input"))
      (node (ref "C2") (pin "2") (pinfunction "2_2") (pintype "unspecified"))
      (node (ref "C3") (pin "2") (pinfunction "2_2") (pintype "unspecified"))
      (node (ref "C4") (pin "1") (pinfunction "1_1") (pintype "unspecified"))
      (node (ref "C5") (pin "1") (pinfunction "1_1") (pintype "unspecified"))
      (node (ref "C6") (pin "1") (pinfunction "1_1") (pintype "unspecified"))
      (node (ref "C7") (pin "1") (pinfunction "1_1") (pintype "unspecified"))
      (node (ref "C8") (pin "1") (pinfunction "1_1") (pintype "unspecified"))
      (node (ref "C9") (pin "1") (pinfunction "1_1") (pintype "unspecified"))
      (node (ref "INV1") (pin "7") (pinfunction "GND_7") (pintype "unspecified"))
      (node (ref "INV2") (pin "7") (pinfunction "GND_7") (pintype "unspecified"))
      (node (ref "INV3") (pin "7") (pinfunction "GND_7") (pintype "unspecified"))
      (node (ref "J1") (pin "1") (pinfunction "1_1") (pintype "unspecified"))
      (node (ref "J2") (pin "10") (pinfunction "10_10") (pintype "unspecified"))
      (node (ref "J3") (pin "2") (pinfunction "2_2") (pintype "unspecified"))
      (node (ref "J5") (pin "2") (pinfunction "2_2") (pintype "unspecified"))
      (node (ref "J6") (pin "2") (pinfunction "2_2") (pintype "unspecified"))
      (node (ref "J7") (pin "2") (pinfunction "2_2") (pintype "unspecified"))
      (node (ref "J8") (pin "1") (pinfunction "1_1") (pintype "input"))
      (node (ref "NOR1") (pin "7") (pinfunction "GND_7") (pintype "unspecified"))
      (node (ref "NOR2") (pin "7") (pinfunction "GND_7") (pintype "unspecified"))
      (node (ref "NOR3") (pin "7") (pinfunction "GND_7") (pintype "unspecified"))
      (node (ref "R1") (pin "1") (pinfunction "1_1") (pintype "unspecified"))
      (node (ref "R10") (pin "1") (pinfunction "1_1") (pintype "unspecified"))
      (node (ref "R2") (pin "1") (pinfunction "1_1") (pintype "unspecified"))
      (node (ref "R3") (pin "1") (pinfunction "1_1") (pintype "unspecified"))
      (node (ref "R4") (pin "1") (pinfunction "1_1") (pintype "unspecified"))
      (node (ref "R5") (pin "1") (pinfunction "1_1") (pintype "unspecified"))
      (node (ref "R6") (pin "1") (pinfunction "1_1") (pintype "unspecified"))
      (node (ref "R7") (pin "1") (pinfunction "1_1") (pintype "unspecified"))
      (node (ref "R8") (pin "1") (pinfunction "1_1") (pintype "unspecified"))
      (node (ref "R9") (pin "1") (pinfunction "1_1") (pintype "unspecified"))
      (node (ref "RAM1") (pin "14") (pinfunction "Vss_14") (pintype "unspecified"))
      (node (ref "REG1") (pin "1") (pinfunction "OC#_1") (pintype "unspecified"))
      (node (ref "REG1") (pin "10") (pinfunction "GND_10") (pintype "unspecified"))
      (node (ref "REG2") (pin "1") (pinfunction "OC#_1") (pintype "unspecified"))
      (node (ref "REG2") (pin "10") (pinfunction "GND_10") (pintype "unspecified"))
      (node (ref "REG_A") (pin "1") (pinfunction "OC#_1") (pintype "unspecified"))
      (node (ref "REG_A") (pin "10") (pinfunction "GND_10") (pintype "unspecified"))
      (node (ref "REG_B") (pin "1") (pinfunction "OC#_1") (pintype "unspecified"))
      (node (ref "REG_B") (pin "10") (pinfunction "GND_10") (pintype "unspecified"))
      (node (ref "REG_IRO") (pin "1") (pinfunction "OC#_1") (pintype "unspecified"))
      (node (ref "REG_IRO") (pin "10") (pinfunction "GND_10") (pintype "unspecified"))
      (node (ref "REG_RP") (pin "1") (pinfunction "OC#_1") (pintype "unspecified"))
      (node (ref "REG_RP") (pin "10") (pinfunction "GND_10") (pintype "unspecified"))
      (node (ref "ROM1") (pin "16") (pinfunction "VSS_16") (pintype "unspecified"))
      (node (ref "ROM1") (pin "22") (pinfunction "CE#_22") (pintype "unspecified"))
      (node (ref "ROM1") (pin "24") (pinfunction "OE#_24") (pintype "unspecified"))
      (node (ref "ROM2") (pin "16") (pinfunction "VSS_16") (pintype "unspecified"))
      (node (ref "ROM2") (pin "22") (pinfunction "CE#_22") (pintype "unspecified"))
      (node (ref "ROM2") (pin "24") (pinfunction "OE#_24") (pintype "unspecified"))
      (node (ref "U1") (pin "1") (pinfunction "GND_1") (pintype "unspecified"))
      (node (ref "XOR1") (pin "7") (pinfunction "GND_7") (pintype "unspecified"))
      (node (ref "XOR2") (pin "7") (pinfunction "GND_7") (pintype "unspecified"))
      (node (ref "XOR3") (pin "7") (pinfunction "GND_7") (pintype "unspecified"))
      (node (ref "XOR4") (pin "7") (pinfunction "GND_7") (pintype "unspecified"))
      (node (ref "XOR5") (pin "7") (pinfunction "GND_7") (pintype "unspecified"))
      (node (ref "XOR6") (pin "7") (pinfunction "GND_7") (pintype "unspecified"))
    )
    (net (code "77") (name "IR0") (class "Default")
      (node (ref "AND1") (pin "1") (pinfunction "1A_1") (pintype "unspecified"))
      (node (ref "J12") (pin "1") (pinfunction "1_1") (pintype "unspecified"))
      (node (ref "REG1") (pin "2") (pinfunction "1Q_2") (pintype "unspecified"))
      (node (ref "ROM1") (pin "12") (pinfunction "A0_12") (pintype "unspecified"))
      (node (ref "ROM2") (pin "12") (pinfunction "A0_12") (pintype "unspecified"))
      (node (ref "XOR1") (pin "1") (pinfunction "1A_1") (pintype "unspecified"))
    )
    (net (code "78") (name "IR1") (class "Default")
      (node (ref "AND1") (pin "4") (pinfunction "2A_4") (pintype "unspecified"))
      (node (ref "J12") (pin "2") (pinfunction "2_2") (pintype "unspecified"))
      (node (ref "REG1") (pin "5") (pinfunction "2Q_5") (pintype "unspecified"))
      (node (ref "ROM1") (pin "11") (pinfunction "A1_11") (pintype "unspecified"))
      (node (ref "ROM2") (pin "11") (pinfunction "A1_11") (pintype "unspecified"))
      (node (ref "XOR1") (pin "4") (pinfunction "2A_4") (pintype "unspecified"))
    )
    (net (code "79") (name "IR2") (class "Default")
      (node (ref "AND1") (pin "9") (pinfunction "3A_9") (pintype "unspecified"))
      (node (ref "J12") (pin "3") (pinfunction "3_3") (pintype "unspecified"))
      (node (ref "REG1") (pin "6") (pinfunction "3Q_6") (pintype "unspecified"))
      (node (ref "ROM1") (pin "10") (pinfunction "A2_10") (pintype "unspecified"))
      (node (ref "ROM2") (pin "10") (pinfunction "A2_10") (pintype "unspecified"))
      (node (ref "XOR1") (pin "9") (pinfunction "3A_9") (pintype "unspecified"))
    )
    (net (code "80") (name "IR3") (class "Default")
      (node (ref "AND1") (pin "12") (pinfunction "4A_12") (pintype "unspecified"))
      (node (ref "J12") (pin "4") (pinfunction "4_4") (pintype "unspecified"))
      (node (ref "REG1") (pin "9") (pinfunction "4Q_9") (pintype "unspecified"))
      (node (ref "ROM1") (pin "9") (pinfunction "A3_9") (pintype "unspecified"))
      (node (ref "ROM2") (pin "9") (pinfunction "A3_9") (pintype "unspecified"))
      (node (ref "XOR1") (pin "12") (pinfunction "4A_12") (pintype "unspecified"))
    )
    (net (code "81") (name "IR4") (class "Default")
      (node (ref "AND2") (pin "1") (pinfunction "1A_1") (pintype "unspecified"))
      (node (ref "J12") (pin "5") (pinfunction "5_5") (pintype "unspecified"))
      (node (ref "REG1") (pin "12") (pinfunction "5Q_12") (pintype "unspecified"))
      (node (ref "ROM1") (pin "8") (pinfunction "A4_8") (pintype "unspecified"))
      (node (ref "ROM2") (pin "8") (pinfunction "A4_8") (pintype "unspecified"))
      (node (ref "XOR2") (pin "1") (pinfunction "1A_1") (pintype "unspecified"))
    )
    (net (code "82") (name "IR5") (class "Default")
      (node (ref "AND2") (pin "4") (pinfunction "2A_4") (pintype "unspecified"))
      (node (ref "J12") (pin "6") (pinfunction "6_6") (pintype "unspecified"))
      (node (ref "REG1") (pin "15") (pinfunction "6Q_15") (pintype "unspecified"))
      (node (ref "ROM1") (pin "7") (pinfunction "A5_7") (pintype "unspecified"))
      (node (ref "ROM2") (pin "7") (pinfunction "A5_7") (pintype "unspecified"))
      (node (ref "XOR2") (pin "4") (pinfunction "2A_4") (pintype "unspecified"))
    )
    (net (code "83") (name "IR6") (class "Default")
      (node (ref "AND2") (pin "9") (pinfunction "3A_9") (pintype "unspecified"))
      (node (ref "J12") (pin "7") (pinfunction "7_7") (pintype "unspecified"))
      (node (ref "REG1") (pin "16") (pinfunction "7Q_16") (pintype "unspecified"))
      (node (ref "ROM1") (pin "6") (pinfunction "A6_6") (pintype "unspecified"))
      (node (ref "ROM2") (pin "6") (pinfunction "A6_6") (pintype "unspecified"))
      (node (ref "XOR2") (pin "9") (pinfunction "3A_9") (pintype "unspecified"))
    )
    (net (code "84") (name "IR7") (class "Default")
      (node (ref "AND2") (pin "12") (pinfunction "4A_12") (pintype "unspecified"))
      (node (ref "J12") (pin "8") (pinfunction "8_8") (pintype "unspecified"))
      (node (ref "REG1") (pin "19") (pinfunction "8Q_19") (pintype "unspecified"))
      (node (ref "ROM1") (pin "5") (pinfunction "A7_5") (pintype "unspecified"))
      (node (ref "ROM2") (pin "5") (pinfunction "A7_5") (pintype "unspecified"))
      (node (ref "XOR2") (pin "12") (pinfunction "4A_12") (pintype "unspecified"))
    )
    (net (code "85") (name "IR8") (class "Default")
      (node (ref "AND3") (pin "1") (pinfunction "1A_1") (pintype "unspecified"))
      (node (ref "J13") (pin "1") (pinfunction "1_1") (pintype "unspecified"))
      (node (ref "REG2") (pin "2") (pinfunction "1Q_2") (pintype "unspecified"))
      (node (ref "ROM1") (pin "27") (pinfunction "A8_27") (pintype "unspecified"))
      (node (ref "ROM2") (pin "27") (pinfunction "A8_27") (pintype "unspecified"))
      (node (ref "XOR3") (pin "1") (pinfunction "1A_1") (pintype "unspecified"))
    )
    (net (code "86") (name "IR9") (class "Default")
      (node (ref "AND3") (pin "4") (pinfunction "2A_4") (pintype "unspecified"))
      (node (ref "J13") (pin "2") (pinfunction "2_2") (pintype "unspecified"))
      (node (ref "REG2") (pin "5") (pinfunction "2Q_5") (pintype "unspecified"))
      (node (ref "ROM1") (pin "26") (pinfunction "A9_26") (pintype "unspecified"))
      (node (ref "ROM2") (pin "26") (pinfunction "A9_26") (pintype "unspecified"))
      (node (ref "XOR3") (pin "4") (pinfunction "2A_4") (pintype "unspecified"))
    )
    (net (code "87") (name "IR10") (class "Default")
      (node (ref "AND3") (pin "9") (pinfunction "3A_9") (pintype "unspecified"))
      (node (ref "J13") (pin "3") (pinfunction "3_3") (pintype "unspecified"))
      (node (ref "REG2") (pin "6") (pinfunction "3Q_6") (pintype "unspecified"))
      (node (ref "ROM1") (pin "23") (pinfunction "A10_23") (pintype "unspecified"))
      (node (ref "ROM2") (pin "23") (pinfunction "A10_23") (pintype "unspecified"))
      (node (ref "XOR3") (pin "9") (pinfunction "3A_9") (pintype "unspecified"))
    )
    (net (code "88") (name "IR11") (class "Default")
      (node (ref "AND3") (pin "12") (pinfunction "4A_12") (pintype "unspecified"))
      (node (ref "J13") (pin "4") (pinfunction "4_4") (pintype "unspecified"))
      (node (ref "REG2") (pin "9") (pinfunction "4Q_9") (pintype "unspecified"))
      (node (ref "ROM1") (pin "25") (pinfunction "A11_25") (pintype "unspecified"))
      (node (ref "ROM2") (pin "25") (pinfunction "A11_25") (pintype "unspecified"))
      (node (ref "XOR3") (pin "12") (pinfunction "4A_12") (pintype "unspecified"))
    )
    (net (code "89") (name "IR12") (class "Default")
      (node (ref "AND4") (pin "1") (pinfunction "1A_1") (pintype "unspecified"))
      (node (ref "J13") (pin "5") (pinfunction "5_5") (pintype "unspecified"))
      (node (ref "REG2") (pin "12") (pinfunction "5Q_12") (pintype "unspecified"))
      (node (ref "ROM1") (pin "4") (pinfunction "A12_4") (pintype "unspecified"))
      (node (ref "ROM2") (pin "4") (pinfunction "A12_4") (pintype "unspecified"))
      (node (ref "XOR4") (pin "1") (pinfunction "1A_1") (pintype "unspecified"))
    )
    (net (code "90") (name "IR13") (class "Default")
      (node (ref "AND4") (pin "4") (pinfunction "2A_4") (pintype "unspecified"))
      (node (ref "J13") (pin "6") (pinfunction "6_6") (pintype "unspecified"))
      (node (ref "REG2") (pin "15") (pinfunction "6Q_15") (pintype "unspecified"))
      (node (ref "ROM1") (pin "28") (pinfunction "A13_28") (pintype "unspecified"))
      (node (ref "ROM2") (pin "28") (pinfunction "A13_28") (pintype "unspecified"))
      (node (ref "XOR4") (pin "4") (pinfunction "2A_4") (pintype "unspecified"))
    )
    (net (code "91") (name "IR14") (class "Default")
      (node (ref "AND4") (pin "9") (pinfunction "3A_9") (pintype "unspecified"))
      (node (ref "J13") (pin "7") (pinfunction "7_7") (pintype "unspecified"))
      (node (ref "REG2") (pin "16") (pinfunction "7Q_16") (pintype "unspecified"))
      (node (ref "ROM1") (pin "29") (pinfunction "A14_29") (pintype "unspecified"))
      (node (ref "ROM2") (pin "29") (pinfunction "A14_29") (pintype "unspecified"))
      (node (ref "XOR4") (pin "9") (pinfunction "3A_9") (pintype "unspecified"))
    )
    (net (code "92") (name "IR15") (class "Default")
      (node (ref "AND4") (pin "12") (pinfunction "4A_12") (pintype "unspecified"))
      (node (ref "J13") (pin "8") (pinfunction "8_8") (pintype "unspecified"))
      (node (ref "REG2") (pin "19") (pinfunction "8Q_19") (pintype "unspecified"))
      (node (ref "ROM1") (pin "3") (pinfunction "A15_3") (pintype "unspecified"))
      (node (ref "ROM2") (pin "3") (pinfunction "A15_3") (pintype "unspecified"))
      (node (ref "XOR4") (pin "12") (pinfunction "4A_12") (pintype "unspecified"))
    )
    (net (code "93") (name "IRC0") (class "Default")
      (node (ref "AND1") (pin "3") (pinfunction "1Y_3") (pintype "unspecified"))
      (node (ref "AND1") (pin "5") (pinfunction "2B_5") (pintype "unspecified"))
      (node (ref "XOR1") (pin "5") (pinfunction "2B_5") (pintype "unspecified"))
    )
    (net (code "94") (name "IRC1") (class "Default")
      (node (ref "AND1") (pin "10") (pinfunction "3B_10") (pintype "unspecified"))
      (node (ref "AND1") (pin "6") (pinfunction "2Y_6") (pintype "unspecified"))
      (node (ref "XOR1") (pin "10") (pinfunction "3B_10") (pintype "unspecified"))
    )
    (net (code "95") (name "IRC2") (class "Default")
      (node (ref "AND1") (pin "13") (pinfunction "4B_13") (pintype "unspecified"))
      (node (ref "AND1") (pin "8") (pinfunction "3Y_8") (pintype "unspecified"))
      (node (ref "XOR1") (pin "13") (pinfunction "4B_13") (pintype "unspecified"))
    )
    (net (code "96") (name "IRC3") (class "Default")
      (node (ref "AND1") (pin "11") (pinfunction "4Y_11") (pintype "unspecified"))
      (node (ref "AND2") (pin "2") (pinfunction "1B_2") (pintype "unspecified"))
      (node (ref "XOR2") (pin "2") (pinfunction "1B_2") (pintype "unspecified"))
    )
    (net (code "97") (name "IRC4") (class "Default")
      (node (ref "AND2") (pin "3") (pinfunction "1Y_3") (pintype "unspecified"))
      (node (ref "AND2") (pin "5") (pinfunction "2B_5") (pintype "unspecified"))
      (node (ref "XOR2") (pin "5") (pinfunction "2B_5") (pintype "unspecified"))
    )
    (net (code "98") (name "IRC5") (class "Default")
      (node (ref "AND2") (pin "10") (pinfunction "3B_10") (pintype "unspecified"))
      (node (ref "AND2") (pin "6") (pinfunction "2Y_6") (pintype "unspecified"))
      (node (ref "XOR2") (pin "10") (pinfunction "3B_10") (pintype "unspecified"))
    )
    (net (code "99") (name "IRC6") (class "Default")
      (node (ref "AND2") (pin "13") (pinfunction "4B_13") (pintype "unspecified"))
      (node (ref "AND2") (pin "8") (pinfunction "3Y_8") (pintype "unspecified"))
      (node (ref "XOR2") (pin "13") (pinfunction "4B_13") (pintype "unspecified"))
    )
    (net (code "100") (name "IRC7") (class "Default")
      (node (ref "AND2") (pin "11") (pinfunction "4Y_11") (pintype "unspecified"))
      (node (ref "AND3") (pin "2") (pinfunction "1B_2") (pintype "unspecified"))
      (node (ref "XOR3") (pin "2") (pinfunction "1B_2") (pintype "unspecified"))
    )
    (net (code "101") (name "IRC8") (class "Default")
      (node (ref "AND3") (pin "3") (pinfunction "1Y_3") (pintype "unspecified"))
      (node (ref "AND3") (pin "5") (pinfunction "2B_5") (pintype "unspecified"))
      (node (ref "XOR3") (pin "5") (pinfunction "2B_5") (pintype "unspecified"))
    )
    (net (code "102") (name "IRC9") (class "Default")
      (node (ref "AND3") (pin "10") (pinfunction "3B_10") (pintype "unspecified"))
      (node (ref "AND3") (pin "6") (pinfunction "2Y_6") (pintype "unspecified"))
      (node (ref "XOR3") (pin "10") (pinfunction "3B_10") (pintype "unspecified"))
    )
    (net (code "103") (name "IRC10") (class "Default")
      (node (ref "AND3") (pin "13") (pinfunction "4B_13") (pintype "unspecified"))
      (node (ref "AND3") (pin "8") (pinfunction "3Y_8") (pintype "unspecified"))
      (node (ref "XOR3") (pin "13") (pinfunction "4B_13") (pintype "unspecified"))
    )
    (net (code "104") (name "IRC11") (class "Default")
      (node (ref "AND3") (pin "11") (pinfunction "4Y_11") (pintype "unspecified"))
      (node (ref "AND4") (pin "2") (pinfunction "1B_2") (pintype "unspecified"))
      (node (ref "XOR4") (pin "2") (pinfunction "1B_2") (pintype "unspecified"))
    )
    (net (code "105") (name "IRC12") (class "Default")
      (node (ref "AND4") (pin "3") (pinfunction "1Y_3") (pintype "unspecified"))
      (node (ref "AND4") (pin "5") (pinfunction "2B_5") (pintype "unspecified"))
      (node (ref "XOR4") (pin "5") (pinfunction "2B_5") (pintype "unspecified"))
    )
    (net (code "106") (name "IRC13") (class "Default")
      (node (ref "AND4") (pin "10") (pinfunction "3B_10") (pintype "unspecified"))
      (node (ref "AND4") (pin "6") (pinfunction "2Y_6") (pintype "unspecified"))
      (node (ref "XOR4") (pin "10") (pinfunction "3B_10") (pintype "unspecified"))
    )
    (net (code "107") (name "IRC14") (class "Default")
      (node (ref "AND4") (pin "13") (pinfunction "4B_13") (pintype "unspecified"))
      (node (ref "AND4") (pin "8") (pinfunction "3Y_8") (pintype "unspecified"))
      (node (ref "XOR4") (pin "13") (pinfunction "4B_13") (pintype "unspecified"))
    )
    (net (code "108") (name "IRC15") (class "Default")
      (node (ref "AND4") (pin "11") (pinfunction "4Y_11") (pintype "unspecified"))
      (node (ref "J15") (pin "2") (pinfunction "2_2") (pintype "unspecified"))
    )
    (net (code "109") (name "IRI0") (class "Default")
      (node (ref "BUF1") (pin "2") (pinfunction "1A_2") (pintype "unspecified"))
      (node (ref "XOR1") (pin "3") (pinfunction "1Y_3") (pintype "unspecified"))
    )
    (net (code "110") (name "IRI1") (class "Default")
      (node (ref "BUF1") (pin "5") (pinfunction "2A_5") (pintype "unspecified"))
      (node (ref "XOR1") (pin "6") (pinfunction "2Y_6") (pintype "unspecified"))
    )
    (net (code "111") (name "IRI2") (class "Default")
      (node (ref "BUF1") (pin "9") (pinfunction "3A_9") (pintype "unspecified"))
      (node (ref "XOR1") (pin "8") (pinfunction "3Y_8") (pintype "unspecified"))
    )
    (net (code "112") (name "IRI3") (class "Default")
      (node (ref "BUF1") (pin "12") (pinfunction "4A_12") (pintype "unspecified"))
      (node (ref "XOR1") (pin "11") (pinfunction "4Y_11") (pintype "unspecified"))
    )
    (net (code "113") (name "IRI4") (class "Default")
      (node (ref "BUF2") (pin "2") (pinfunction "1A_2") (pintype "unspecified"))
      (node (ref "XOR2") (pin "3") (pinfunction "1Y_3") (pintype "unspecified"))
    )
    (net (code "114") (name "IRI5") (class "Default")
      (node (ref "BUF2") (pin "5") (pinfunction "2A_5") (pintype "unspecified"))
      (node (ref "XOR2") (pin "6") (pinfunction "2Y_6") (pintype "unspecified"))
    )
    (net (code "115") (name "IRI6") (class "Default")
      (node (ref "BUF2") (pin "9") (pinfunction "3A_9") (pintype "unspecified"))
      (node (ref "XOR2") (pin "8") (pinfunction "3Y_8") (pintype "unspecified"))
    )
    (net (code "116") (name "IRI7") (class "Default")
      (node (ref "BUF2") (pin "12") (pinfunction "4A_12") (pintype "unspecified"))
      (node (ref "XOR2") (pin "11") (pinfunction "4Y_11") (pintype "unspecified"))
    )
    (net (code "117") (name "IRI8") (class "Default")
      (node (ref "BUF3") (pin "2") (pinfunction "1A_2") (pintype "unspecified"))
      (node (ref "XOR3") (pin "3") (pinfunction "1Y_3") (pintype "unspecified"))
    )
    (net (code "118") (name "IRI9") (class "Default")
      (node (ref "BUF3") (pin "5") (pinfunction "2A_5") (pintype "unspecified"))
      (node (ref "XOR3") (pin "6") (pinfunction "2Y_6") (pintype "unspecified"))
    )
    (net (code "119") (name "IRI10") (class "Default")
      (node (ref "BUF3") (pin "9") (pinfunction "3A_9") (pintype "unspecified"))
      (node (ref "XOR3") (pin "8") (pinfunction "3Y_8") (pintype "unspecified"))
    )
    (net (code "120") (name "IRI11") (class "Default")
      (node (ref "BUF3") (pin "12") (pinfunction "4A_12") (pintype "unspecified"))
      (node (ref "XOR3") (pin "11") (pinfunction "4Y_11") (pintype "unspecified"))
    )
    (net (code "121") (name "IRI12") (class "Default")
      (node (ref "BUF4") (pin "2") (pinfunction "1A_2") (pintype "unspecified"))
      (node (ref "XOR4") (pin "3") (pinfunction "1Y_3") (pintype "unspecified"))
    )
    (net (code "122") (name "IRI13") (class "Default")
      (node (ref "BUF4") (pin "5") (pinfunction "2A_5") (pintype "unspecified"))
      (node (ref "XOR4") (pin "6") (pinfunction "2Y_6") (pintype "unspecified"))
    )
    (net (code "123") (name "IRI14") (class "Default")
      (node (ref "BUF4") (pin "9") (pinfunction "3A_9") (pintype "unspecified"))
      (node (ref "XOR4") (pin "8") (pinfunction "3Y_8") (pintype "unspecified"))
    )
    (net (code "124") (name "IRI15") (class "Default")
      (node (ref "BUF4") (pin "12") (pinfunction "4A_12") (pintype "unspecified"))
      (node (ref "XOR4") (pin "11") (pinfunction "4Y_11") (pintype "unspecified"))
    )
    (net (code "125") (name "IR_IN0") (class "Default")
      (node (ref "BUF1") (pin "3") (pinfunction "1Y_3") (pintype "unspecified"))
      (node (ref "BUF5") (pin "3") (pinfunction "1Y_3") (pintype "unspecified"))
      (node (ref "R2") (pin "2") (pinfunction "2_2") (pintype "unspecified"))
      (node (ref "REG1") (pin "3") (pinfunction "1D_3") (pintype "unspecified"))
    )
    (net (code "126") (name "IR_IN1") (class "Default")
      (node (ref "BUF1") (pin "6") (pinfunction "2Y_6") (pintype "unspecified"))
      (node (ref "BUF5") (pin "6") (pinfunction "2Y_6") (pintype "unspecified"))
      (node (ref "R3") (pin "2") (pinfunction "2_2") (pintype "unspecified"))
      (node (ref "REG1") (pin "4") (pinfunction "2D_4") (pintype "unspecified"))
    )
    (net (code "127") (name "IR_IN2") (class "Default")
      (node (ref "BUF1") (pin "8") (pinfunction "3Y_8") (pintype "unspecified"))
      (node (ref "BUF5") (pin "8") (pinfunction "3Y_8") (pintype "unspecified"))
      (node (ref "R4") (pin "2") (pinfunction "2_2") (pintype "unspecified"))
      (node (ref "REG1") (pin "7") (pinfunction "3D_7") (pintype "unspecified"))
    )
    (net (code "128") (name "IR_IN3") (class "Default")
      (node (ref "BUF1") (pin "11") (pinfunction "4Y_11") (pintype "unspecified"))
      (node (ref "BUF5") (pin "11") (pinfunction "4Y_11") (pintype "unspecified"))
      (node (ref "R5") (pin "2") (pinfunction "2_2") (pintype "unspecified"))
      (node (ref "REG1") (pin "8") (pinfunction "4D_8") (pintype "unspecified"))
    )
    (net (code "129") (name "IR_IN4") (class "Default")
      (node (ref "BUF2") (pin "3") (pinfunction "1Y_3") (pintype "unspecified"))
      (node (ref "BUF6") (pin "3") (pinfunction "1Y_3") (pintype "unspecified"))
      (node (ref "R6") (pin "2") (pinfunction "2_2") (pintype "unspecified"))
      (node (ref "REG1") (pin "13") (pinfunction "5D_13") (pintype "unspecified"))
    )
    (net (code "130") (name "IR_IN5") (class "Default")
      (node (ref "BUF2") (pin "6") (pinfunction "2Y_6") (pintype "unspecified"))
      (node (ref "BUF6") (pin "6") (pinfunction "2Y_6") (pintype "unspecified"))
      (node (ref "R7") (pin "2") (pinfunction "2_2") (pintype "unspecified"))
      (node (ref "REG1") (pin "14") (pinfunction "6D_14") (pintype "unspecified"))
    )
    (net (code "131") (name "IR_IN6") (class "Default")
      (node (ref "BUF2") (pin "8") (pinfunction "3Y_8") (pintype "unspecified"))
      (node (ref "BUF6") (pin "8") (pinfunction "3Y_8") (pintype "unspecified"))
      (node (ref "R8") (pin "2") (pinfunction "2_2") (pintype "unspecified"))
      (node (ref "REG1") (pin "17") (pinfunction "7D_17") (pintype "unspecified"))
    )
    (net (code "132") (name "IR_IN7") (class "Default")
      (node (ref "BUF2") (pin "11") (pinfunction "4Y_11") (pintype "unspecified"))
      (node (ref "BUF6") (pin "11") (pinfunction "4Y_11") (pintype "unspecified"))
      (node (ref "R9") (pin "2") (pinfunction "2_2") (pintype "unspecified"))
      (node (ref "REG1") (pin "18") (pinfunction "8D_18") (pintype "unspecified"))
    )
    (net (code "133") (name "IR_IN8") (class "Default")
      (node (ref "BUF3") (pin "3") (pinfunction "1Y_3") (pintype "unspecified"))
      (node (ref "BUF7") (pin "3") (pinfunction "1Y_3") (pintype "unspecified"))
      (node (ref "REG2") (pin "3") (pinfunction "1D_3") (pintype "unspecified"))
    )
    (net (code "134") (name "IR_IN9") (class "Default")
      (node (ref "BUF3") (pin "6") (pinfunction "2Y_6") (pintype "unspecified"))
      (node (ref "BUF7") (pin "6") (pinfunction "2Y_6") (pintype "unspecified"))
      (node (ref "REG2") (pin "4") (pinfunction "2D_4") (pintype "unspecified"))
    )
    (net (code "135") (name "IR_IN10") (class "Default")
      (node (ref "BUF3") (pin "8") (pinfunction "3Y_8") (pintype "unspecified"))
      (node (ref "BUF7") (pin "8") (pinfunction "3Y_8") (pintype "unspecified"))
      (node (ref "REG2") (pin "7") (pinfunction "3D_7") (pintype "unspecified"))
    )
    (net (code "136") (name "IR_IN11") (class "Default")
      (node (ref "BUF3") (pin "11") (pinfunction "4Y_11") (pintype "unspecified"))
      (node (ref "BUF7") (pin "11") (pinfunction "4Y_11") (pintype "unspecified"))
      (node (ref "REG2") (pin "8") (pinfunction "4D_8") (pintype "unspecified"))
    )
    (net (code "137") (name "IR_IN12") (class "Default")
      (node (ref "BUF4") (pin "3") (pinfunction "1Y_3") (pintype "unspecified"))
      (node (ref "BUF8") (pin "3") (pinfunction "1Y_3") (pintype "unspecified"))
      (node (ref "REG2") (pin "13") (pinfunction "5D_13") (pintype "unspecified"))
    )
    (net (code "138") (name "IR_IN13") (class "Default")
      (node (ref "BUF4") (pin "6") (pinfunction "2Y_6") (pintype "unspecified"))
      (node (ref "BUF8") (pin "6") (pinfunction "2Y_6") (pintype "unspecified"))
      (node (ref "REG2") (pin "14") (pinfunction "6D_14") (pintype "unspecified"))
    )
    (net (code "139") (name "IR_IN14") (class "Default")
      (node (ref "BUF4") (pin "8") (pinfunction "3Y_8") (pintype "unspecified"))
      (node (ref "BUF8") (pin "8") (pinfunction "3Y_8") (pintype "unspecified"))
      (node (ref "REG2") (pin "17") (pinfunction "7D_17") (pintype "unspecified"))
    )
    (net (code "140") (name "IR_IN15") (class "Default")
      (node (ref "BUF4") (pin "11") (pinfunction "4Y_11") (pintype "unspecified"))
      (node (ref "BUF8") (pin "11") (pinfunction "4Y_11") (pintype "unspecified"))
      (node (ref "REG2") (pin "18") (pinfunction "8D_18") (pintype "unspecified"))
    )
    (net (code "141") (name "IR_O8") (class "Default")
      (node (ref "BUF7") (pin "2") (pinfunction "1A_2") (pintype "unspecified"))
      (node (ref "REG_IRO") (pin "2") (pinfunction "1Q_2") (pintype "unspecified"))
    )
    (net (code "142") (name "IR_O9") (class "Default")
      (node (ref "BUF7") (pin "5") (pinfunction "2A_5") (pintype "unspecified"))
      (node (ref "REG_IRO") (pin "5") (pinfunction "2Q_5") (pintype "unspecified"))
    )
    (net (code "143") (name "IR_O10") (class "Default")
      (node (ref "BUF7") (pin "9") (pinfunction "3A_9") (pintype "unspecified"))
      (node (ref "REG_IRO") (pin "6") (pinfunction "3Q_6") (pintype "unspecified"))
    )
    (net (code "144") (name "IR_O11") (class "Default")
      (node (ref "BUF7") (pin "12") (pinfunction "4A_12") (pintype "unspecified"))
      (node (ref "REG_IRO") (pin "9") (pinfunction "4Q_9") (pintype "unspecified"))
    )
    (net (code "145") (name "IR_O12") (class "Default")
      (node (ref "BUF8") (pin "2") (pinfunction "1A_2") (pintype "unspecified"))
      (node (ref "REG_IRO") (pin "12") (pinfunction "5Q_12") (pintype "unspecified"))
    )
    (net (code "146") (name "IR_O13") (class "Default")
      (node (ref "BUF8") (pin "5") (pinfunction "2A_5") (pintype "unspecified"))
      (node (ref "REG_IRO") (pin "15") (pinfunction "6Q_15") (pintype "unspecified"))
    )
    (net (code "147") (name "IR_O14") (class "Default")
      (node (ref "BUF8") (pin "9") (pinfunction "3A_9") (pintype "unspecified"))
      (node (ref "REG_IRO") (pin "16") (pinfunction "7Q_16") (pintype "unspecified"))
    )
    (net (code "148") (name "IR_O15") (class "Default")
      (node (ref "BUF8") (pin "12") (pinfunction "4A_12") (pintype "unspecified"))
      (node (ref "REG_IRO") (pin "19") (pinfunction "8Q_19") (pintype "unspecified"))
    )
    (net (code "149") (name "IR_OE") (class "Default")
      (node (ref "BUF5") (pin "1") (pinfunction "1G_1") (pintype "unspecified"))
      (node (ref "BUF5") (pin "10") (pinfunction "3G_10") (pintype "unspecified"))
      (node (ref "BUF5") (pin "13") (pinfunction "4G_13") (pintype "unspecified"))
      (node (ref "BUF5") (pin "4") (pinfunction "2G_4") (pintype "unspecified"))
      (node (ref "BUF6") (pin "1") (pinfunction "1G_1") (pintype "unspecified"))
      (node (ref "BUF6") (pin "10") (pinfunction "3G_10") (pintype "unspecified"))
      (node (ref "BUF6") (pin "13") (pinfunction "4G_13") (pintype "unspecified"))
      (node (ref "BUF6") (pin "4") (pinfunction "2G_4") (pintype "unspecified"))
      (node (ref "BUF7") (pin "1") (pinfunction "1G_1") (pintype "unspecified"))
      (node (ref "BUF7") (pin "10") (pinfunction "3G_10") (pintype "unspecified"))
      (node (ref "BUF7") (pin "13") (pinfunction "4G_13") (pintype "unspecified"))
      (node (ref "BUF7") (pin "4") (pinfunction "2G_4") (pintype "unspecified"))
      (node (ref "BUF8") (pin "1") (pinfunction "1G_1") (pintype "unspecified"))
      (node (ref "BUF8") (pin "10") (pinfunction "3G_10") (pintype "unspecified"))
      (node (ref "BUF8") (pin "13") (pinfunction "4G_13") (pintype "unspecified"))
      (node (ref "BUF8") (pin "4") (pinfunction "2G_4") (pintype "unspecified"))
      (node (ref "NOR2") (pin "4") (pinfunction "2A_4") (pintype "unspecified"))
      (node (ref "NOR3") (pin "6") (pinfunction "2Y_6") (pintype "unspecified"))
    )
    (net (code "150") (name "IR_OE_INV") (class "Default")
      (node (ref "BUF1") (pin "1") (pinfunction "1G_1") (pintype "unspecified"))
      (node (ref "BUF1") (pin "10") (pinfunction "3G_10") (pintype "unspecified"))
      (node (ref "BUF1") (pin "13") (pinfunction "4G_13") (pintype "unspecified"))
      (node (ref "BUF1") (pin "4") (pinfunction "2G_4") (pintype "unspecified"))
      (node (ref "BUF2") (pin "1") (pinfunction "1G_1") (pintype "unspecified"))
      (node (ref "BUF2") (pin "10") (pinfunction "3G_10") (pintype "unspecified"))
      (node (ref "BUF2") (pin "13") (pinfunction "4G_13") (pintype "unspecified"))
      (node (ref "BUF2") (pin "4") (pinfunction "2G_4") (pintype "unspecified"))
      (node (ref "BUF3") (pin "1") (pinfunction "1G_1") (pintype "unspecified"))
      (node (ref "BUF3") (pin "10") (pinfunction "3G_10") (pintype "unspecified"))
      (node (ref "BUF3") (pin "13") (pinfunction "4G_13") (pintype "unspecified"))
      (node (ref "BUF3") (pin "4") (pinfunction "2G_4") (pintype "unspecified"))
      (node (ref "BUF4") (pin "1") (pinfunction "1G_1") (pintype "unspecified"))
      (node (ref "BUF4") (pin "10") (pinfunction "3G_10") (pintype "unspecified"))
      (node (ref "BUF4") (pin "13") (pinfunction "4G_13") (pintype "unspecified"))
      (node (ref "BUF4") (pin "4") (pinfunction "2G_4") (pintype "unspecified"))
      (node (ref "NOR2") (pin "6") (pinfunction "2Y_6") (pintype "unspecified"))
    )
    (net (code "151") (name "LIT0") (class "Default")
      (node (ref "BUF9") (pin "2") (pinfunction "1A_2") (pintype "unspecified"))
      (node (ref "J11") (pin "1") (pinfunction "1_1") (pintype "unspecified"))
      (node (ref "ROM2") (pin "13") (pinfunction "DQ0_13") (pintype "unspecified"))
    )
    (net (code "152") (name "LIT1") (class "Default")
      (node (ref "BUF9") (pin "5") (pinfunction "2A_5") (pintype "unspecified"))
      (node (ref "J11") (pin "2") (pinfunction "2_2") (pintype "unspecified"))
      (node (ref "ROM2") (pin "14") (pinfunction "DQ1_14") (pintype "unspecified"))
    )
    (net (code "153") (name "LIT2") (class "Default")
      (node (ref "BUF9") (pin "9") (pinfunction "3A_9") (pintype "unspecified"))
      (node (ref "J11") (pin "3") (pinfunction "3_3") (pintype "unspecified"))
      (node (ref "ROM2") (pin "15") (pinfunction "DQ2_15") (pintype "unspecified"))
    )
    (net (code "154") (name "LIT3") (class "Default")
      (node (ref "BUF9") (pin "12") (pinfunction "4A_12") (pintype "unspecified"))
      (node (ref "J11") (pin "4") (pinfunction "4_4") (pintype "unspecified"))
      (node (ref "ROM2") (pin "17") (pinfunction "DQ3_17") (pintype "unspecified"))
    )
    (net (code "155") (name "LIT4") (class "Default")
      (node (ref "BUF10") (pin "2") (pinfunction "1A_2") (pintype "unspecified"))
      (node (ref "J11") (pin "5") (pinfunction "5_5") (pintype "unspecified"))
      (node (ref "ROM2") (pin "18") (pinfunction "DQ4_18") (pintype "unspecified"))
    )
    (net (code "156") (name "LIT5") (class "Default")
      (node (ref "BUF10") (pin "5") (pinfunction "2A_5") (pintype "unspecified"))
      (node (ref "J11") (pin "6") (pinfunction "6_6") (pintype "unspecified"))
      (node (ref "ROM2") (pin "19") (pinfunction "DQ5_19") (pintype "unspecified"))
    )
    (net (code "157") (name "LIT6") (class "Default")
      (node (ref "BUF10") (pin "9") (pinfunction "3A_9") (pintype "unspecified"))
      (node (ref "J11") (pin "7") (pinfunction "7_7") (pintype "unspecified"))
      (node (ref "ROM2") (pin "20") (pinfunction "DQ6_20") (pintype "unspecified"))
    )
    (net (code "158") (name "LIT7") (class "Default")
      (node (ref "BUF10") (pin "12") (pinfunction "4A_12") (pintype "unspecified"))
      (node (ref "J11") (pin "8") (pinfunction "8_8") (pintype "unspecified"))
      (node (ref "ROM2") (pin "21") (pinfunction "DQ7_21") (pintype "unspecified"))
    )
    (net (code "159") (name "LIT_EN") (class "Default")
      (node (ref "BUF10") (pin "1") (pinfunction "1G_1") (pintype "unspecified"))
      (node (ref "BUF10") (pin "10") (pinfunction "3G_10") (pintype "unspecified"))
      (node (ref "BUF10") (pin "13") (pinfunction "4G_13") (pintype "unspecified"))
      (node (ref "BUF10") (pin "4") (pinfunction "2G_4") (pintype "unspecified"))
      (node (ref "BUF9") (pin "1") (pinfunction "1G_1") (pintype "unspecified"))
      (node (ref "BUF9") (pin "10") (pinfunction "3G_10") (pintype "unspecified"))
      (node (ref "BUF9") (pin "13") (pinfunction "4G_13") (pintype "unspecified"))
      (node (ref "BUF9") (pin "4") (pinfunction "2G_4") (pintype "unspecified"))
      (node (ref "NOR1") (pin "6") (pinfunction "2Y_6") (pintype "unspecified"))
    )
    (net (code "160") (name "Net-(ADD1-C4)") (class "Default")
      (node (ref "ADD1") (pin "9") (pinfunction "C4_9") (pintype "unspecified"))
      (node (ref "ADD2") (pin "7") (pinfunction "C0_7") (pintype "unspecified"))
    )
    (net (code "161") (name "Net-(AND5-1Y)") (class "Default")
      (node (ref "AND5") (pin "3") (pinfunction "1Y_3") (pintype "unspecified"))
      (node (ref "INV3") (pin "13") (pinfunction "6A_13") (pintype "unspecified"))
    )
    (net (code "162") (name "Net-(AND5-2Y)") (class "Default")
      (node (ref "AND5") (pin "6") (pinfunction "2Y_6") (pintype "unspecified"))
      (node (ref "INV3") (pin "11") (pinfunction "5A_11") (pintype "unspecified"))
    )
    (net (code "163") (name "Net-(AND6-2B)") (class "Default")
      (node (ref "AND6") (pin "10") (pinfunction "3B_10") (pintype "unspecified"))
      (node (ref "AND6") (pin "13") (pinfunction "4B_13") (pintype "unspecified"))
      (node (ref "AND6") (pin "5") (pinfunction "2B_5") (pintype "unspecified"))
      (node (ref "NOR1") (pin "5") (pinfunction "1Y_5") (pintype "unspecified"))
    )
    (net (code "164") (name "Net-(AND9-1A)") (class "Default")
      (node (ref "AND9") (pin "1") (pinfunction "1A_1") (pintype "unspecified"))
      (node (ref "INV3") (pin "12") (pinfunction "6Y_12") (pintype "unspecified"))
    )
    (net (code "165") (name "Net-(AND9-1Y)") (class "Default")
      (node (ref "AND9") (pin "3") (pinfunction "1Y_3") (pintype "unspecified"))
      (node (ref "NOR3") (pin "1") (pinfunction "1A_1") (pintype "unspecified"))
    )
    (net (code "166") (name "Net-(AND9-2A)") (class "Default")
      (node (ref "AND9") (pin "4") (pinfunction "2A_4") (pintype "unspecified"))
      (node (ref "INV3") (pin "10") (pinfunction "5Y_10") (pintype "unspecified"))
    )
    (net (code "167") (name "Net-(AND9-2Y)") (class "Default")
      (node (ref "AND9") (pin "6") (pinfunction "2Y_6") (pintype "unspecified"))
      (node (ref "NOR3") (pin "4") (pinfunction "2A_4") (pintype "unspecified"))
    )
    (net (code "168") (name "Net-(J1-Pad2)") (class "Default")
      (node (ref "J1") (pin "2") (pinfunction "2_2") (pintype "unspecified"))
      (node (ref "SW3") (pin "1") (pinfunction "1_1") (pintype "unspecified"))
    )
    (net (code "169") (name "Net-(J3-Pad1)") (class "Default")
      (node (ref "J3") (pin "1") (pinfunction "1_1") (pintype "unspecified"))
      (node (ref "J4") (pin "1") (pinfunction "1_1") (pintype "unspecified"))
    )
    (net (code "170") (name "Net-(R1-Pad2)") (class "Default")
      (node (ref "R1") (pin "2") (pinfunction "2_2") (pintype "unspecified"))
      (node (ref "SW1") (pin "4") (pinfunction "4_4") (pintype "unspecified"))
      (node (ref "SW2") (pin "1") (pinfunction "1_1") (pintype "unspecified"))
    )
    (net (code "171") (name "Net-(R12-Pad1)") (class "Default")
      (node (ref "R12") (pin "1") (pinfunction "1_1") (pintype "unspecified"))
      (node (ref "R13") (pin "2") (pinfunction "2_2") (pintype "input"))
    )
    (net (code "172") (name "Net-(SW2-Pad3)") (class "Default")
      (node (ref "SW2") (pin "3") (pinfunction "3_3") (pintype "unspecified"))
      (node (ref "SW3") (pin "2") (pinfunction "2_2") (pintype "unspecified"))
    )
    (net (code "173") (name "Net-(U1-CONTROLVOLTAGE)") (class "Default")
      (node (ref "C2") (pin "1") (pinfunction "1_1") (pintype "unspecified"))
      (node (ref "U1") (pin "5") (pinfunction "CONTROLVOLTAGE_5") (pintype "unspecified"))
    )
    (net (code "174") (name "Net-(U1-DISCHARGE)") (class "Default")
      (node (ref "R11") (pin "2") (pinfunction "2_2") (pintype "unspecified"))
      (node (ref "R12") (pin "2") (pinfunction "2_2") (pintype "unspecified"))
      (node (ref "U1") (pin "7") (pinfunction "DISCHARGE_7") (pintype "unspecified"))
    )
    (net (code "175") (name "Net-(U1-OUTPUT)") (class "Default")
      (node (ref "SW3") (pin "3") (pinfunction "3_3") (pintype "unspecified"))
      (node (ref "U1") (pin "3") (pinfunction "OUTPUT_3") (pintype "unspecified"))
    )
    (net (code "176") (name "Net-(U1-THRESHOLD)") (class "Default")
      (node (ref "C3") (pin "1") (pinfunction "1_1") (pintype "unspecified"))
      (node (ref "R13") (pin "1") (pinfunction "1_1") (pintype "input"))
      (node (ref "U1") (pin "2") (pinfunction "TRIGGER_2") (pintype "unspecified"))
      (node (ref "U1") (pin "6") (pinfunction "THRESHOLD_6") (pintype "unspecified"))
    )
    (net (code "177") (name "R1") (class "Default")
      (node (ref "AND11") (pin "12") (pinfunction "1Y_12") (pintype "unspecified"))
      (node (ref "INV2") (pin "13") (pinfunction "6A_13") (pintype "unspecified"))
      (node (ref "NOR2") (pin "1") (pinfunction "1A_1") (pintype "unspecified"))
    )
    (net (code "178") (name "R1_INV") (class "Default")
      (node (ref "AND9") (pin "2") (pinfunction "1B_2") (pintype "unspecified"))
      (node (ref "INV2") (pin "12") (pinfunction "6Y_12") (pintype "unspecified"))
    )
    (net (code "179") (name "R2") (class "Default")
      (node (ref "AND11") (pin "6") (pinfunction "2Y_6") (pintype "unspecified"))
      (node (ref "INV3") (pin "9") (pinfunction "4A_9") (pintype "unspecified"))
      (node (ref "NOR2") (pin "2") (pinfunction "1B_2") (pintype "unspecified"))
    )
    (net (code "180") (name "R2_INV") (class "Default")
      (node (ref "AND9") (pin "5") (pinfunction "2B_5") (pintype "unspecified"))
      (node (ref "INV3") (pin "8") (pinfunction "4Y_8") (pintype "unspecified"))
    )
    (net (code "181") (name "R3") (class "Default")
      (node (ref "AND11") (pin "8") (pinfunction "3Y_8") (pintype "unspecified"))
      (node (ref "AND5") (pin "1") (pinfunction "1A_1") (pintype "unspecified"))
      (node (ref "NOR2") (pin "3") (pinfunction "1C_3") (pintype "unspecified"))
    )
    (net (code "182") (name "R4") (class "Default")
      (node (ref "AND12") (pin "12") (pinfunction "1Y_12") (pintype "unspecified"))
      (node (ref "AND5") (pin "4") (pinfunction "2A_4") (pintype "unspecified"))
      (node (ref "NOR2") (pin "12") (pinfunction "1D_12") (pintype "unspecified"))
    )
    (net (code "183") (name "R7") (class "Default")
      (node (ref "AND12") (pin "11") (pinfunction "3C_11") (pintype "unspecified"))
      (node (ref "AND12") (pin "6") (pinfunction "2Y_6") (pintype "unspecified"))
      (node (ref "NOR2") (pin "13") (pinfunction "1E_13") (pintype "unspecified"))
    )
    (net (code "184") (name "RAM_EN") (class "Default")
      (node (ref "INV2") (pin "5") (pinfunction "3A_5") (pintype "unspecified"))
      (node (ref "NOR2") (pin "5") (pinfunction "1Y_5") (pintype "unspecified"))
    )
    (net (code "185") (name "RAM_EN_INV") (class "Default")
      (node (ref "INV2") (pin "6") (pinfunction "3Y_6") (pintype "unspecified"))
      (node (ref "RAM1") (pin "20") (pinfunction "CE#_20") (pintype "unspecified"))
    )
    (net (code "186") (name "READ_A") (class "Default")
      (node (ref "AND5") (pin "8") (pinfunction "3Y_8") (pintype "unspecified"))
      (node (ref "REG_A") (pin "11") (pinfunction "CLK_11") (pintype "unspecified"))
    )
    (net (code "187") (name "READ_B") (class "Default")
      (node (ref "AND5") (pin "11") (pinfunction "4Y_11") (pintype "unspecified"))
      (node (ref "REG_B") (pin "11") (pinfunction "CLK_11") (pintype "unspecified"))
    )
    (net (code "188") (name "READ_IR_O") (class "Default")
      (node (ref "NOR3") (pin "5") (pinfunction "1Y_5") (pintype "unspecified"))
      (node (ref "REG_IRO") (pin "11") (pinfunction "CLK_11") (pintype "unspecified"))
    )
    (net (code "189") (name "READ_RP") (class "Default")
      (node (ref "AND6") (pin "3") (pinfunction "1Y_3") (pintype "unspecified"))
      (node (ref "REG_RP") (pin "11") (pinfunction "CLK_11") (pintype "unspecified"))
    )
    (net (code "190") (name "RP0") (class "Default")
      (node (ref "AND6") (pin "4") (pinfunction "2A_4") (pintype "unspecified"))
      (node (ref "BUF11") (pin "2") (pinfunction "1A_2") (pintype "unspecified"))
      (node (ref "RAM1") (pin "10") (pinfunction "A0_10") (pintype "unspecified"))
      (node (ref "REG_RP") (pin "2") (pinfunction "1Q_2") (pintype "unspecified"))
    )
    (net (code "191") (name "RP1") (class "Default")
      (node (ref "AND6") (pin "9") (pinfunction "3A_9") (pintype "unspecified"))
      (node (ref "BUF11") (pin "5") (pinfunction "2A_5") (pintype "unspecified"))
      (node (ref "RAM1") (pin "9") (pinfunction "A1_9") (pintype "unspecified"))
      (node (ref "REG_RP") (pin "5") (pinfunction "2Q_5") (pintype "unspecified"))
    )
    (net (code "192") (name "RP2") (class "Default")
      (node (ref "AND6") (pin "12") (pinfunction "4A_12") (pintype "unspecified"))
      (node (ref "BUF11") (pin "9") (pinfunction "3A_9") (pintype "unspecified"))
      (node (ref "RAM1") (pin "8") (pinfunction "A2_8") (pintype "unspecified"))
      (node (ref "REG_RP") (pin "6") (pinfunction "3Q_6") (pintype "unspecified"))
    )
    (net (code "193") (name "RP3") (class "Default")
      (node (ref "BUF11") (pin "12") (pinfunction "4A_12") (pintype "unspecified"))
      (node (ref "NOR1") (pin "1") (pinfunction "1A_1") (pintype "unspecified"))
      (node (ref "RAM1") (pin "7") (pinfunction "A3_7") (pintype "unspecified"))
      (node (ref "REG_RP") (pin "9") (pinfunction "4Q_9") (pintype "unspecified"))
    )
    (net (code "194") (name "RP4") (class "Default")
      (node (ref "BUF12") (pin "2") (pinfunction "1A_2") (pintype "unspecified"))
      (node (ref "NOR1") (pin "2") (pinfunction "1B_2") (pintype "unspecified"))
      (node (ref "RAM1") (pin "6") (pinfunction "A4_6") (pintype "unspecified"))
      (node (ref "REG_RP") (pin "12") (pinfunction "5Q_12") (pintype "unspecified"))
    )
    (net (code "195") (name "RP5") (class "Default")
      (node (ref "BUF12") (pin "5") (pinfunction "2A_5") (pintype "unspecified"))
      (node (ref "NOR1") (pin "3") (pinfunction "1C_3") (pintype "unspecified"))
      (node (ref "RAM1") (pin "5") (pinfunction "A5_5") (pintype "unspecified"))
      (node (ref "REG_RP") (pin "15") (pinfunction "6Q_15") (pintype "unspecified"))
    )
    (net (code "196") (name "RP6") (class "Default")
      (node (ref "BUF12") (pin "9") (pinfunction "3A_9") (pintype "unspecified"))
      (node (ref "NOR1") (pin "12") (pinfunction "1D_12") (pintype "unspecified"))
      (node (ref "RAM1") (pin "4") (pinfunction "A6_4") (pintype "unspecified"))
      (node (ref "REG_RP") (pin "16") (pinfunction "7Q_16") (pintype "unspecified"))
    )
    (net (code "197") (name "RP7") (class "Default")
      (node (ref "BUF12") (pin "12") (pinfunction "4A_12") (pintype "unspecified"))
      (node (ref "NOR1") (pin "13") (pinfunction "1E_13") (pintype "unspecified"))
      (node (ref "RAM1") (pin "3") (pinfunction "A7_3") (pintype "unspecified"))
      (node (ref "REG_RP") (pin "19") (pinfunction "8Q_19") (pintype "unspecified"))
    )
    (net (code "198") (name "RST") (class "Default")
      (node (ref "J7") (pin "1") (pinfunction "1_1") (pintype "unspecified"))
      (node (ref "NOR2") (pin "8") (pinfunction "2B_8") (pintype "unspecified"))
      (node (ref "R10") (pin "2") (pinfunction "2_2") (pintype "unspecified"))
      (node (ref "SW4") (pin "4") (pinfunction "4_4") (pintype "unspecified"))
    )
    (net (code "199") (name "VCC") (class "Default")
      (node (ref "ADD1") (pin "16") (pinfunction "VCC_16") (pintype "unspecified"))
      (node (ref "ADD2") (pin "16") (pinfunction "VCC_16") (pintype "unspecified"))
      (node (ref "AND1") (pin "14") (pinfunction "VCC_14") (pintype "unspecified"))
      (node (ref "AND1") (pin "2") (pinfunction "1B_2") (pintype "unspecified"))
      (node (ref "AND11") (pin "14") (pinfunction "VCC_14") (pintype "unspecified"))
      (node (ref "AND12") (pin "14") (pinfunction "VCC_14") (pintype "unspecified"))
      (node (ref "AND2") (pin "14") (pinfunction "VCC_14") (pintype "unspecified"))
      (node (ref "AND3") (pin "14") (pinfunction "VCC_14") (pintype "unspecified"))
      (node (ref "AND4") (pin "14") (pinfunction "VCC_14") (pintype "unspecified"))
      (node (ref "AND5") (pin "14") (pinfunction "VCC_14") (pintype "unspecified"))
      (node (ref "AND6") (pin "14") (pinfunction "VCC_14") (pintype "unspecified"))
      (node (ref "AND7") (pin "14") (pinfunction "VCC_14") (pintype "unspecified"))
      (node (ref "AND8") (pin "14") (pinfunction "VCC_14") (pintype "unspecified"))
      (node (ref "AND8") (pin "2") (pinfunction "1B_2") (pintype "unspecified"))
      (node (ref "AND9") (pin "14") (pinfunction "VCC_14") (pintype "unspecified"))
      (node (ref "BUF1") (pin "14") (pinfunction "VCC_14") (pintype "unspecified"))
      (node (ref "BUF10") (pin "14") (pinfunction "VCC_14") (pintype "unspecified"))
      (node (ref "BUF11") (pin "14") (pinfunction "VCC_14") (pintype "unspecified"))
      (node (ref "BUF12") (pin "14") (pinfunction "VCC_14") (pintype "unspecified"))
      (node (ref "BUF13") (pin "14") (pinfunction "VCC_14") (pintype "unspecified"))
      (node (ref "BUF14") (pin "14") (pinfunction "VCC_14") (pintype "unspecified"))
      (node (ref "BUF15") (pin "14") (pinfunction "VCC_14") (pintype "unspecified"))
      (node (ref "BUF16") (pin "14") (pinfunction "VCC_14") (pintype "unspecified"))
      (node (ref "BUF2") (pin "14") (pinfunction "VCC_14") (pintype "unspecified"))
      (node (ref "BUF3") (pin "14") (pinfunction "VCC_14") (pintype "unspecified"))
      (node (ref "BUF4") (pin "14") (pinfunction "VCC_14") (pintype "unspecified"))
      (node (ref "BUF5") (pin "14") (pinfunction "VCC_14") (pintype "unspecified"))
      (node (ref "BUF6") (pin "14") (pinfunction "VCC_14") (pintype "unspecified"))
      (node (ref "BUF7") (pin "14") (pinfunction "VCC_14") (pintype "unspecified"))
      (node (ref "BUF8") (pin "14") (pinfunction "VCC_14") (pintype "unspecified"))
      (node (ref "BUF9") (pin "14") (pinfunction "VCC_14") (pintype "unspecified"))
      (node (ref "C1") (pin "2") (pinfunction "2_2") (pintype "unspecified"))
      (node (ref "C10") (pin "2") (pinfunction "2_2") (pintype "unspecified"))
      (node (ref "C11") (pin "2") (pinfunction "2_2") (pintype "unspecified"))
      (node (ref "C12") (pin "2") (pinfunction "2_2") (pintype "unspecified"))
      (node (ref "C13") (pin "2") (pinfunction "2_2") (pintype "unspecified"))
      (node (ref "C14") (pin "2") (pinfunction "2_2") (pintype "unspecified"))
      (node (ref "C15") (pin "1") (pinfunction "1_1") (pintype "input"))
      (node (ref "C4") (pin "2") (pinfunction "2_2") (pintype "unspecified"))
      (node (ref "C5") (pin "2") (pinfunction "2_2") (pintype "unspecified"))
      (node (ref "C6") (pin "2") (pinfunction "2_2") (pintype "unspecified"))
      (node (ref "C7") (pin "2") (pinfunction "2_2") (pintype "unspecified"))
      (node (ref "C8") (pin "2") (pinfunction "2_2") (pintype "unspecified"))
      (node (ref "C9") (pin "2") (pinfunction "2_2") (pintype "unspecified"))
      (node (ref "INV1") (pin "14") (pinfunction "VCC_14") (pintype "unspecified"))
      (node (ref "INV2") (pin "14") (pinfunction "VCC_14") (pintype "unspecified"))
      (node (ref "INV3") (pin "14") (pinfunction "VCC_14") (pintype "unspecified"))
      (node (ref "J4") (pin "2") (pinfunction "2_2") (pintype "unspecified"))
      (node (ref "J5") (pin "1") (pinfunction "1_1") (pintype "unspecified"))
      (node (ref "NOR1") (pin "14") (pinfunction "VCC_14") (pintype "unspecified"))
      (node (ref "NOR2") (pin "14") (pinfunction "VCC_14") (pintype "unspecified"))
      (node (ref "NOR3") (pin "14") (pinfunction "VCC_14") (pintype "unspecified"))
      (node (ref "R11") (pin "1") (pinfunction "1_1") (pintype "unspecified"))
      (node (ref "RAM1") (pin "28") (pinfunction "VCC_28") (pintype "unspecified"))
      (node (ref "REG1") (pin "20") (pinfunction "VCC_20") (pintype "unspecified"))
      (node (ref "REG2") (pin "20") (pinfunction "VCC_20") (pintype "unspecified"))
      (node (ref "REG_A") (pin "20") (pinfunction "VCC_20") (pintype "unspecified"))
      (node (ref "REG_B") (pin "20") (pinfunction "VCC_20") (pintype "unspecified"))
      (node (ref "REG_IRO") (pin "20") (pinfunction "VCC_20") (pintype "unspecified"))
      (node (ref "REG_RP") (pin "20") (pinfunction "VCC_20") (pintype "unspecified"))
      (node (ref "ROM1") (pin "31") (pinfunction "WE#_31") (pintype "unspecified"))
      (node (ref "ROM1") (pin "32") (pinfunction "VDD_32") (pintype "unspecified"))
      (node (ref "ROM2") (pin "31") (pinfunction "WE#_31") (pintype "unspecified"))
      (node (ref "ROM2") (pin "32") (pinfunction "VDD_32") (pintype "unspecified"))
      (node (ref "SW1") (pin "5") (pinfunction "5_5") (pintype "unspecified"))
      (node (ref "SW4") (pin "5") (pinfunction "5_5") (pintype "unspecified"))
      (node (ref "U1") (pin "4") (pinfunction "RESET_4") (pintype "unspecified"))
      (node (ref "U1") (pin "8") (pinfunction "VCC_8") (pintype "unspecified"))
      (node (ref "XOR1") (pin "14") (pinfunction "VCC_14") (pintype "unspecified"))
      (node (ref "XOR1") (pin "2") (pinfunction "1B_2") (pintype "unspecified"))
      (node (ref "XOR2") (pin "14") (pinfunction "VCC_14") (pintype "unspecified"))
      (node (ref "XOR3") (pin "14") (pinfunction "VCC_14") (pintype "unspecified"))
      (node (ref "XOR4") (pin "14") (pinfunction "VCC_14") (pintype "unspecified"))
      (node (ref "XOR5") (pin "14") (pinfunction "VCC_14") (pintype "unspecified"))
      (node (ref "XOR6") (pin "14") (pinfunction "VCC_14") (pintype "unspecified"))
      (node (ref "XOR6") (pin "2") (pinfunction "1B_2") (pintype "unspecified"))
    )
    (net (code "200") (name "unconnected-(ADD2-C4-Pad9)") (class "Default")
      (node (ref "ADD2") (pin "9") (pinfunction "C4_9") (pintype "unspecified+no_connect"))
    )
    (net (code "201") (name "unconnected-(AND9-3A-Pad9)") (class "Default")
      (node (ref "AND9") (pin "9") (pinfunction "3A_9") (pintype "unspecified+no_connect"))
    )
    (net (code "202") (name "unconnected-(AND9-3B-Pad10)") (class "Default")
      (node (ref "AND9") (pin "10") (pinfunction "3B_10") (pintype "unspecified+no_connect"))
    )
    (net (code "203") (name "unconnected-(AND9-3Y-Pad8)") (class "Default")
      (node (ref "AND9") (pin "8") (pinfunction "3Y_8") (pintype "unspecified+no_connect"))
    )
    (net (code "204") (name "unconnected-(AND9-4A-Pad12)") (class "Default")
      (node (ref "AND9") (pin "12") (pinfunction "4A_12") (pintype "unspecified+no_connect"))
    )
    (net (code "205") (name "unconnected-(AND9-4B-Pad13)") (class "Default")
      (node (ref "AND9") (pin "13") (pinfunction "4B_13") (pintype "unspecified+no_connect"))
    )
    (net (code "206") (name "unconnected-(AND9-4Y-Pad11)") (class "Default")
      (node (ref "AND9") (pin "11") (pinfunction "4Y_11") (pintype "unspecified+no_connect"))
    )
    (net (code "207") (name "unconnected-(NOR1-2E-Pad11)") (class "Default")
      (node (ref "NOR1") (pin "11") (pinfunction "2E_11") (pintype "unspecified+no_connect"))
    )
    (net (code "208") (name "unconnected-(NOR2-2C-Pad9)") (class "Default")
      (node (ref "NOR2") (pin "9") (pinfunction "2C_9") (pintype "unspecified+no_connect"))
    )
    (net (code "209") (name "unconnected-(NOR2-2D-Pad10)") (class "Default")
      (node (ref "NOR2") (pin "10") (pinfunction "2D_10") (pintype "unspecified+no_connect"))
    )
    (net (code "210") (name "unconnected-(NOR2-2E-Pad11)") (class "Default")
      (node (ref "NOR2") (pin "11") (pinfunction "2E_11") (pintype "unspecified+no_connect"))
    )
    (net (code "211") (name "unconnected-(NOR3-1C-Pad3)") (class "Default")
      (node (ref "NOR3") (pin "3") (pinfunction "1C_3") (pintype "unspecified+no_connect"))
    )
    (net (code "212") (name "unconnected-(NOR3-1D-Pad12)") (class "Default")
      (node (ref "NOR3") (pin "12") (pinfunction "1D_12") (pintype "unspecified+no_connect"))
    )
    (net (code "213") (name "unconnected-(NOR3-1E-Pad13)") (class "Default")
      (node (ref "NOR3") (pin "13") (pinfunction "1E_13") (pintype "unspecified+no_connect"))
    )
    (net (code "214") (name "unconnected-(NOR3-2C-Pad9)") (class "Default")
      (node (ref "NOR3") (pin "9") (pinfunction "2C_9") (pintype "unspecified+no_connect"))
    )
    (net (code "215") (name "unconnected-(NOR3-2D-Pad10)") (class "Default")
      (node (ref "NOR3") (pin "10") (pinfunction "2D_10") (pintype "unspecified+no_connect"))
    )
    (net (code "216") (name "unconnected-(NOR3-2E-Pad11)") (class "Default")
      (node (ref "NOR3") (pin "11") (pinfunction "2E_11") (pintype "unspecified+no_connect"))
    )
    (net (code "217") (name "unconnected-(R13-Pad3)") (class "Default")
      (node (ref "R13") (pin "3") (pinfunction "3_3") (pintype "input+no_connect"))
    )
    (net (code "218") (name "unconnected-(RAM1-A8-Pad25)") (class "Default")
      (node (ref "RAM1") (pin "25") (pinfunction "A8_25") (pintype "unspecified+no_connect"))
    )
    (net (code "219") (name "unconnected-(RAM1-A9-Pad24)") (class "Default")
      (node (ref "RAM1") (pin "24") (pinfunction "A9_24") (pintype "unspecified+no_connect"))
    )
    (net (code "220") (name "unconnected-(RAM1-A10-Pad21)") (class "Default")
      (node (ref "RAM1") (pin "21") (pinfunction "A10_21") (pintype "unspecified+no_connect"))
    )
    (net (code "221") (name "unconnected-(RAM1-A11-Pad23)") (class "Default")
      (node (ref "RAM1") (pin "23") (pinfunction "A11_23") (pintype "unspecified+no_connect"))
    )
    (net (code "222") (name "unconnected-(RAM1-A12-Pad2)") (class "Default")
      (node (ref "RAM1") (pin "2") (pinfunction "A12_2") (pintype "unspecified+no_connect"))
    )
    (net (code "223") (name "unconnected-(RAM1-A13-Pad26)") (class "Default")
      (node (ref "RAM1") (pin "26") (pinfunction "A13_26") (pintype "unspecified+no_connect"))
    )
    (net (code "224") (name "unconnected-(RAM1-A14-Pad1)") (class "Default")
      (node (ref "RAM1") (pin "1") (pinfunction "A14_1") (pintype "unspecified+no_connect"))
    )
    (net (code "225") (name "unconnected-(ROM1-A16-Pad2)") (class "Default")
      (node (ref "ROM1") (pin "2") (pinfunction "A16_2") (pintype "unspecified+no_connect"))
    )
    (net (code "226") (name "unconnected-(ROM1-A17-Pad30)") (class "Default")
      (node (ref "ROM1") (pin "30") (pinfunction "A17_30") (pintype "unspecified+no_connect"))
    )
    (net (code "227") (name "unconnected-(ROM1-NC-Pad1)") (class "Default")
      (node (ref "ROM1") (pin "1") (pinfunction "NC_1") (pintype "unspecified+no_connect"))
    )
    (net (code "228") (name "unconnected-(ROM2-A16-Pad2)") (class "Default")
      (node (ref "ROM2") (pin "2") (pinfunction "A16_2") (pintype "unspecified+no_connect"))
    )
    (net (code "229") (name "unconnected-(ROM2-A17-Pad30)") (class "Default")
      (node (ref "ROM2") (pin "30") (pinfunction "A17_30") (pintype "unspecified+no_connect"))
    )
    (net (code "230") (name "unconnected-(ROM2-NC-Pad1)") (class "Default")
      (node (ref "ROM2") (pin "1") (pinfunction "NC_1") (pintype "unspecified+no_connect"))
    )
    (net (code "231") (name "unconnected-(SW1-Pad1)") (class "Default")
      (node (ref "SW1") (pin "1") (pinfunction "1_1") (pintype "unspecified+no_connect"))
    )
    (net (code "232") (name "unconnected-(SW1-Pad2)") (class "Default")
      (node (ref "SW1") (pin "2") (pinfunction "2_2") (pintype "unspecified+no_connect"))
    )
    (net (code "233") (name "unconnected-(SW1-Pad3)") (class "Default")
      (node (ref "SW1") (pin "3") (pinfunction "3_3") (pintype "unspecified+no_connect"))
    )
    (net (code "234") (name "unconnected-(SW1-Pad6)") (class "Default")
      (node (ref "SW1") (pin "6") (pinfunction "6_6") (pintype "unspecified+no_connect"))
    )
    (net (code "235") (name "unconnected-(SW2-Pad4)") (class "Default")
      (node (ref "SW2") (pin "4") (pinfunction "4_4") (pintype "unspecified+no_connect"))
    )
    (net (code "236") (name "unconnected-(SW2-Pad5)") (class "Default")
      (node (ref "SW2") (pin "5") (pinfunction "5_5") (pintype "unspecified+no_connect"))
    )
    (net (code "237") (name "unconnected-(SW3-Pad4)") (class "Default")
      (node (ref "SW3") (pin "4") (pinfunction "4_4") (pintype "unspecified+no_connect"))
    )
    (net (code "238") (name "unconnected-(SW3-Pad5)") (class "Default")
      (node (ref "SW3") (pin "5") (pinfunction "5_5") (pintype "unspecified+no_connect"))
    )
    (net (code "239") (name "unconnected-(SW4-Pad1)") (class "Default")
      (node (ref "SW4") (pin "1") (pinfunction "1_1") (pintype "unspecified+no_connect"))
    )
    (net (code "240") (name "unconnected-(SW4-Pad2)") (class "Default")
      (node (ref "SW4") (pin "2") (pinfunction "2_2") (pintype "unspecified+no_connect"))
    )
    (net (code "241") (name "unconnected-(SW4-Pad3)") (class "Default")
      (node (ref "SW4") (pin "3") (pinfunction "3_3") (pintype "unspecified+no_connect"))
    )
    (net (code "242") (name "unconnected-(SW4-Pad6)") (class "Default")
      (node (ref "SW4") (pin "6") (pinfunction "6_6") (pintype "unspecified+no_connect"))
    )
  )
)
